# gld_schematic_v2.net
KiCad netlist of a schematic drawn in EasyEDA
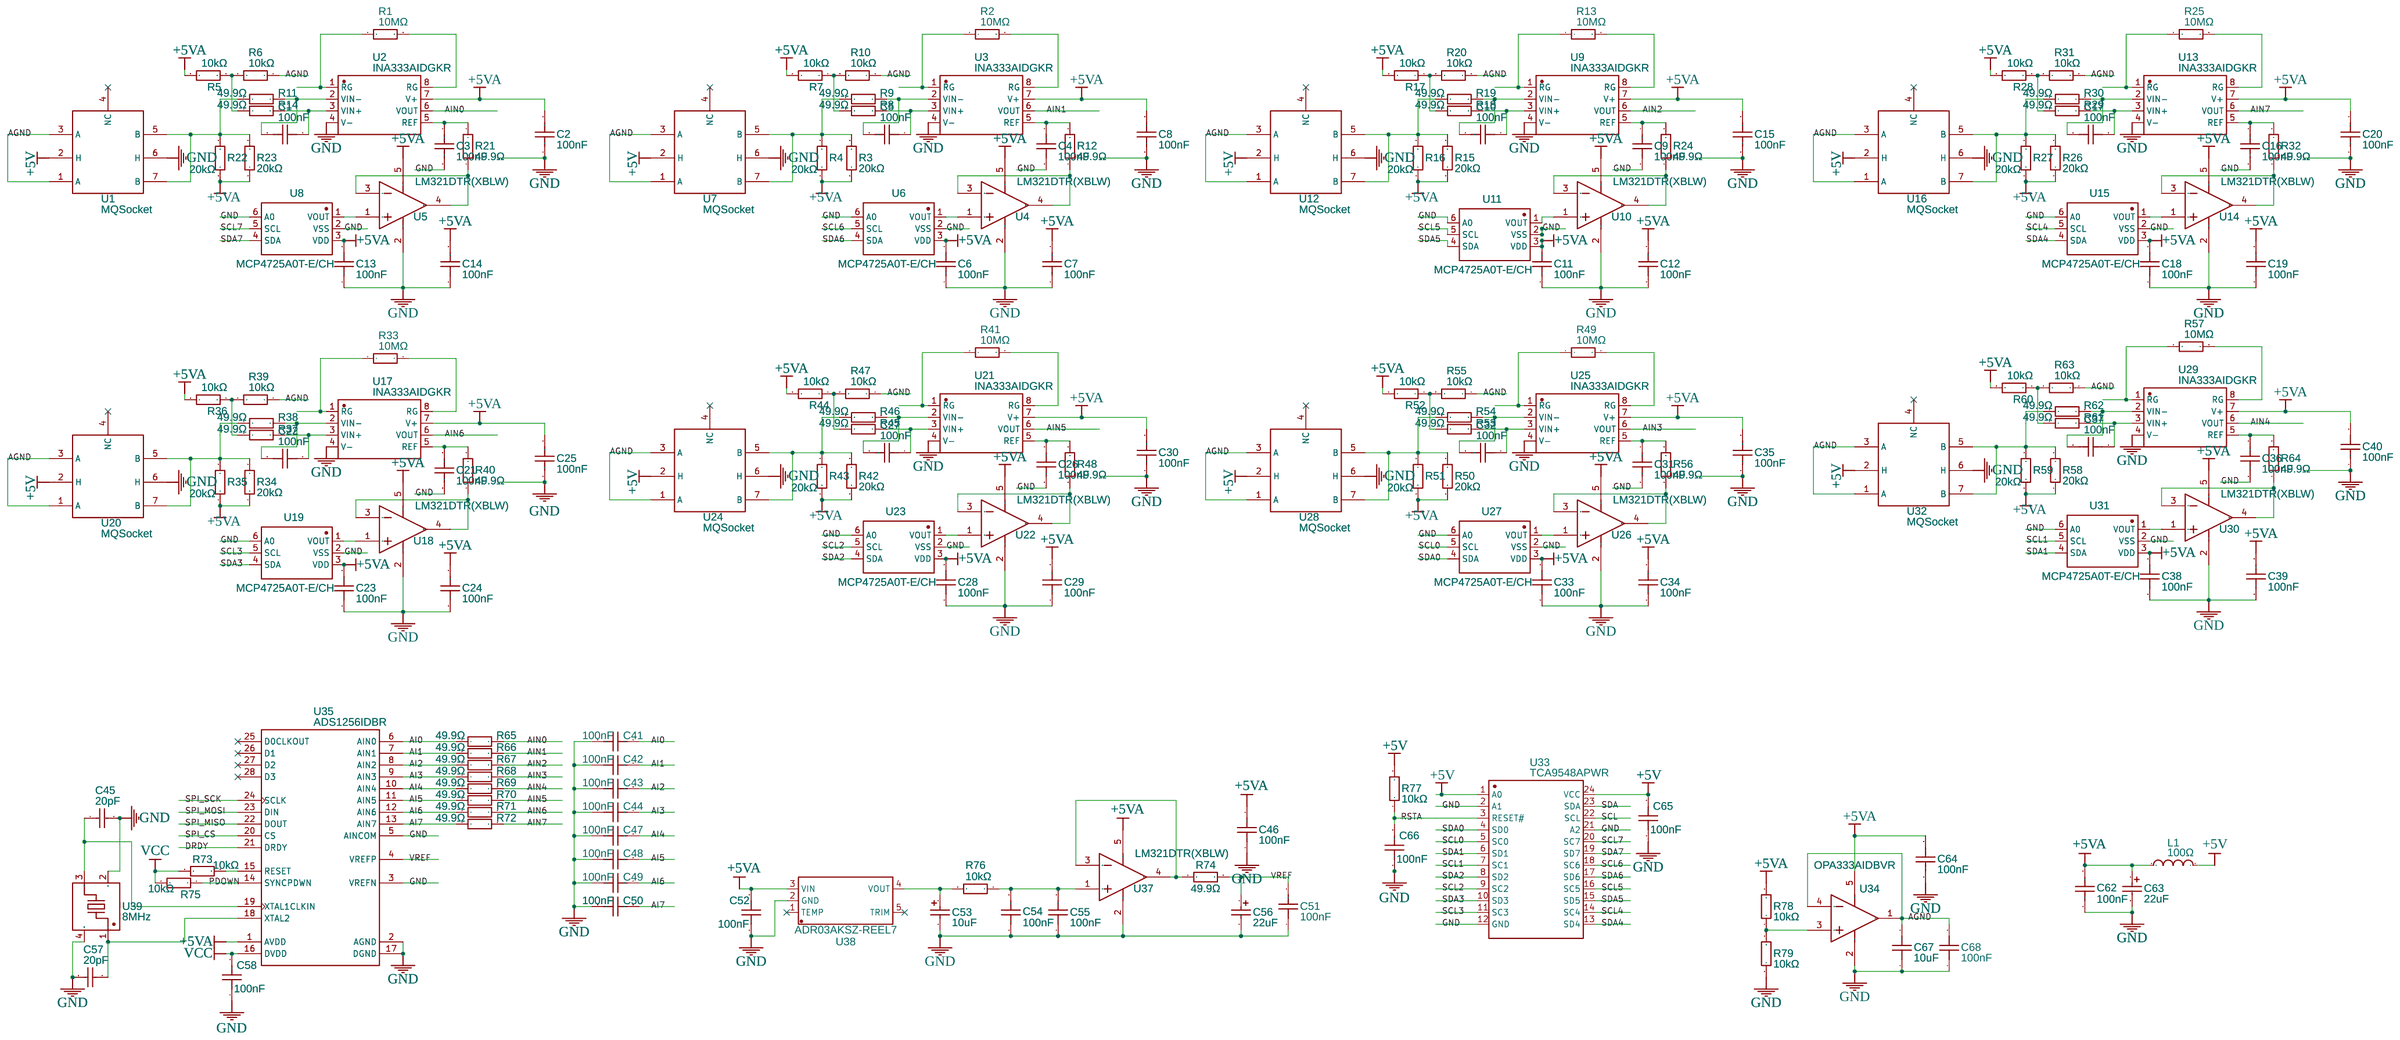
[diagram p0: Sheet_1]
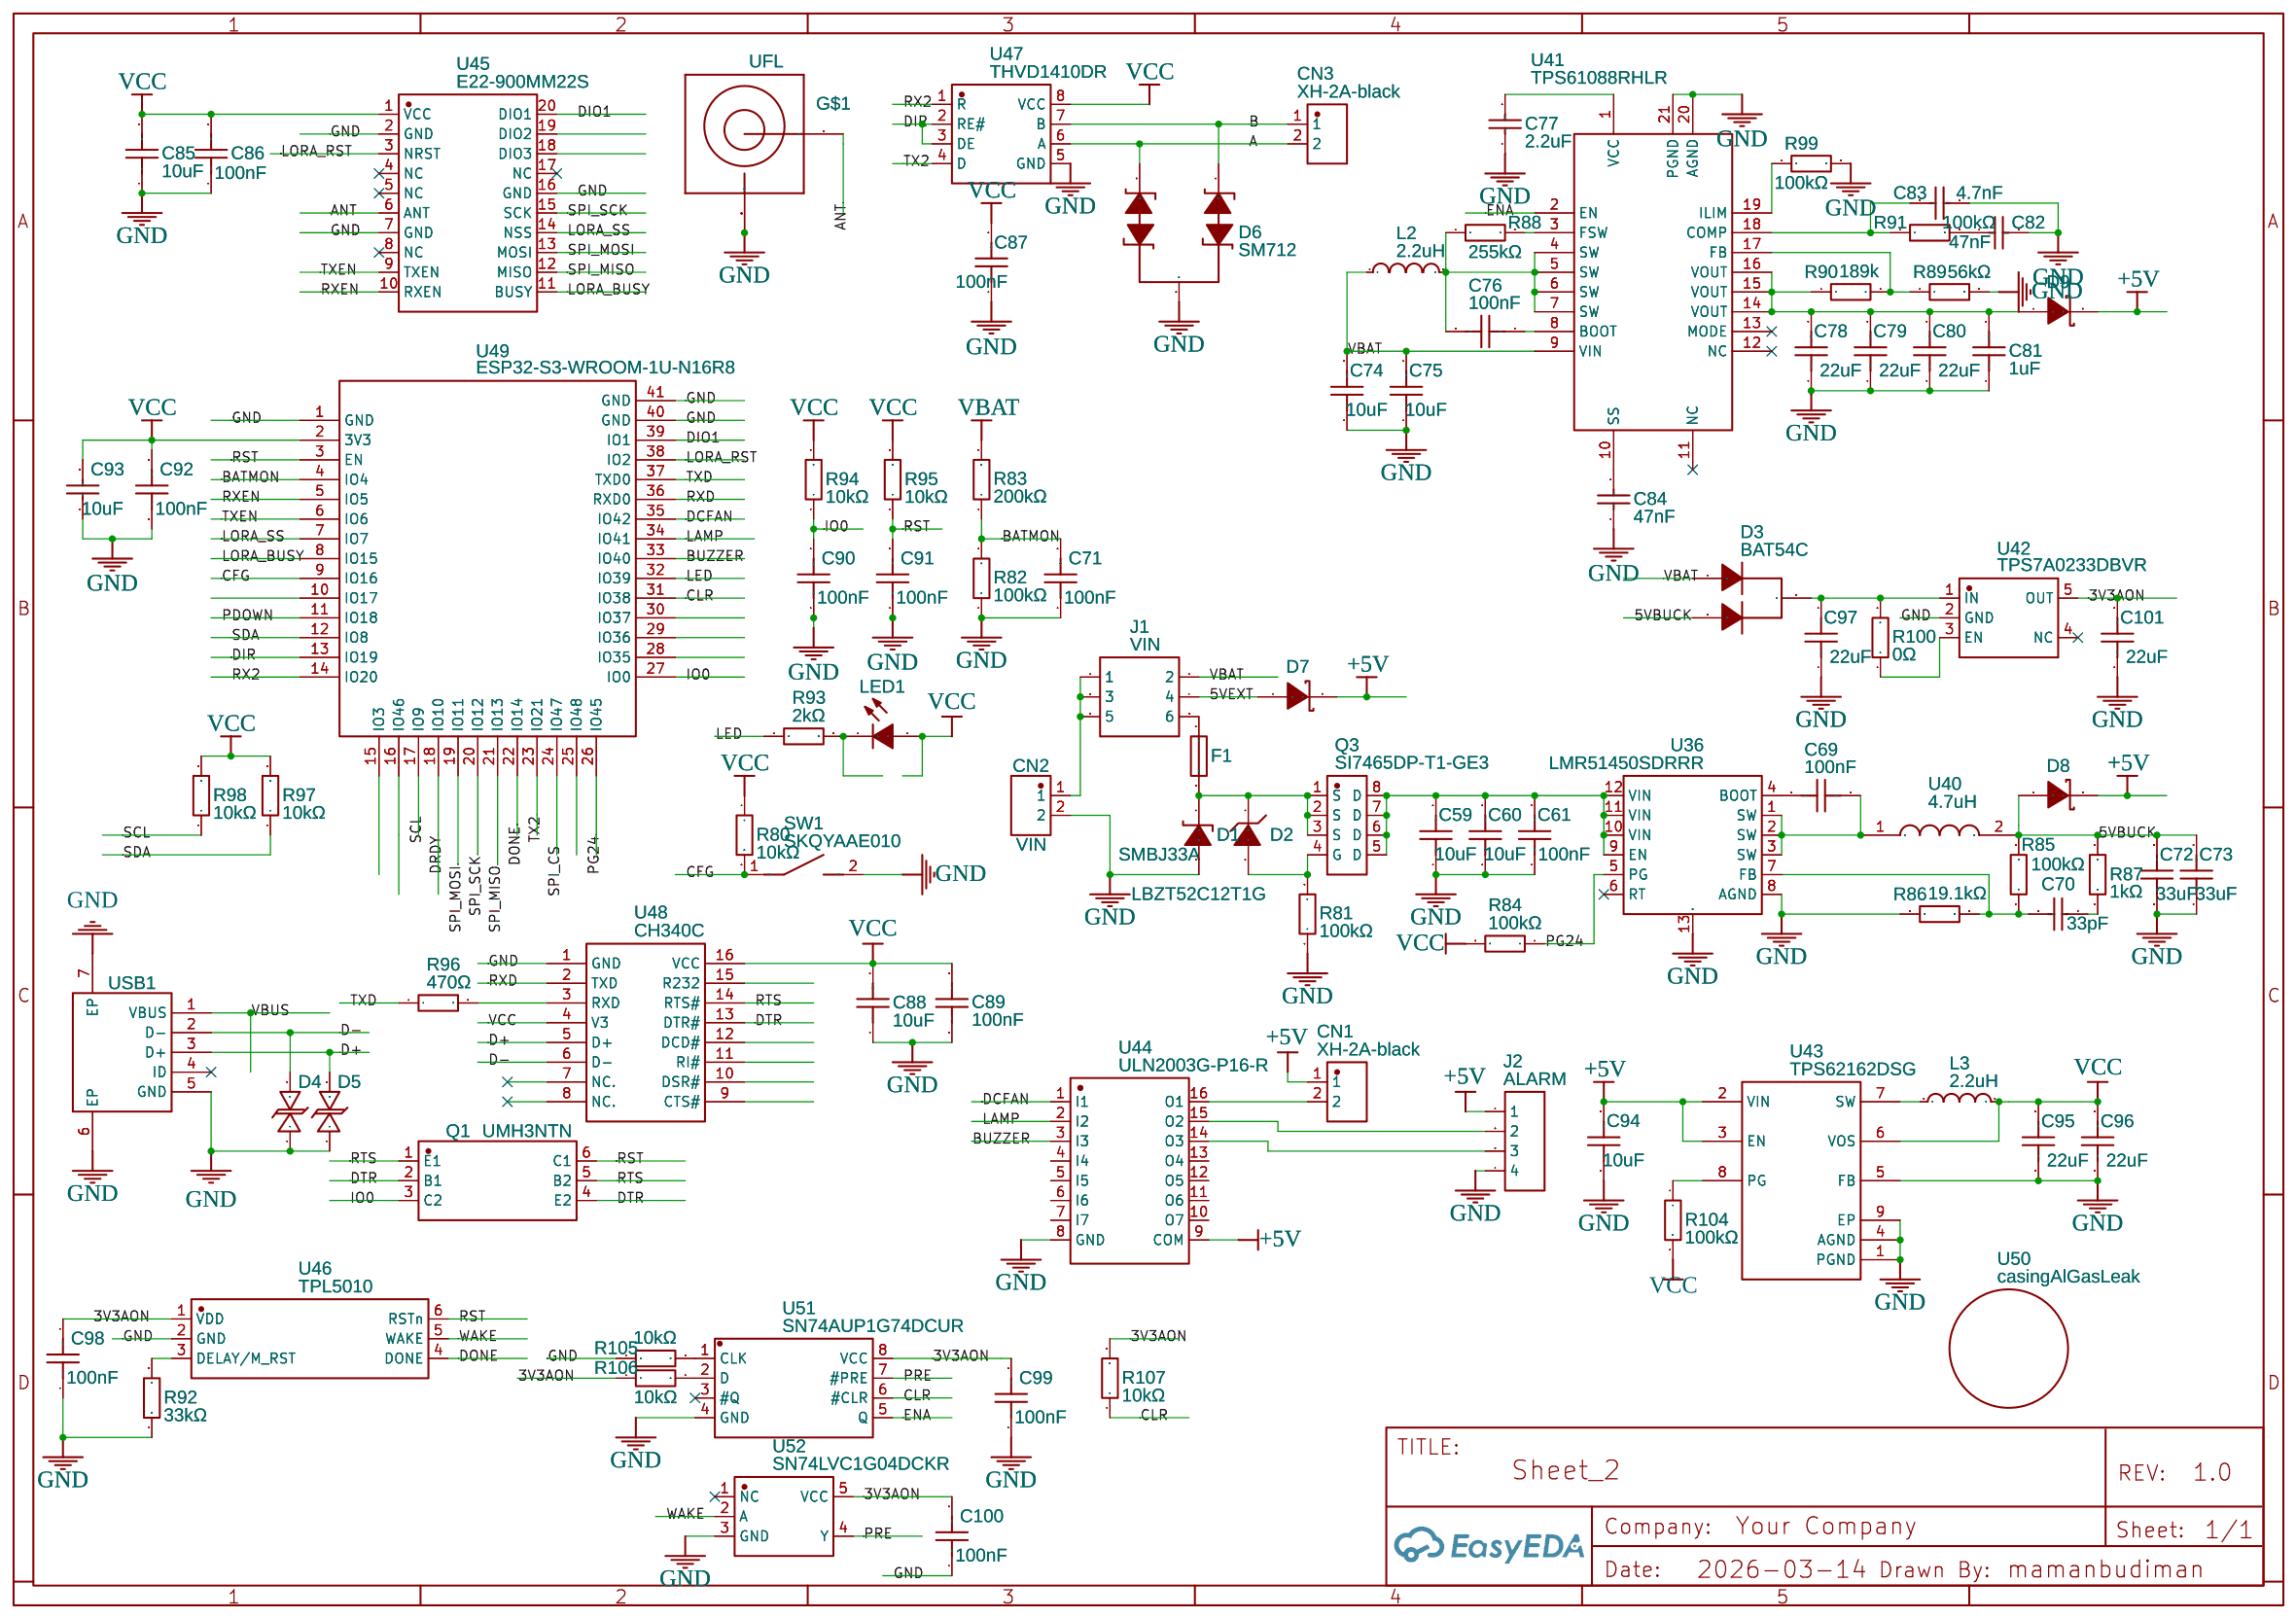
[diagram p1: Sheet_2]

(export (version "E")
  (design (tool "Eeschema 10.0.6"))
  (components
    (comp (ref "C1")
      (value "100nF")
      (fields
        (field (name "Manufacturer Part") "CL05B104KO5NNNC")
        (field (name "Manufacturer") "SAMSUNG(三星)")
      )
      (libsource (lib "") (part "CL05B104KO5NNNC"))
    )
    (comp (ref "C2")
      (value "100nF")
      (fields
        (field (name "Manufacturer Part") "CL05B104KO5NNNC")
        (field (name "Manufacturer") "SAMSUNG(三星)")
      )
      (libsource (lib "") (part "CL05B104KO5NNNC_1"))
    )
    (comp (ref "C3")
      (value "100nF")
      (fields
        (field (name "Manufacturer Part") "CL05B104KO5NNNC")
        (field (name "Manufacturer") "SAMSUNG(三星)")
      )
      (libsource (lib "") (part "CL05B104KO5NNNC_2"))
    )
    (comp (ref "C4")
      (value "100nF")
      (fields
        (field (name "Manufacturer Part") "CL05B104KO5NNNC")
        (field (name "Manufacturer") "SAMSUNG(三星)")
      )
      (libsource (lib "") (part "CL05B104KO5NNNC_2"))
    )
    (comp (ref "C5")
      (value "100nF")
      (fields
        (field (name "Manufacturer Part") "CL05B104KO5NNNC")
        (field (name "Manufacturer") "SAMSUNG(三星)")
      )
      (libsource (lib "") (part "CL05B104KO5NNNC"))
    )
    (comp (ref "C6")
      (value "100nF")
      (fields
        (field (name "Manufacturer Part") "CL05B104KO5NNNC")
        (field (name "Manufacturer") "SAMSUNG(三星)")
      )
      (libsource (lib "") (part "CL05B104KO5NNNC_1"))
    )
    (comp (ref "C7")
      (value "100nF")
      (fields
        (field (name "Manufacturer Part") "CL05B104KO5NNNC")
        (field (name "Manufacturer") "SAMSUNG(三星)")
      )
      (libsource (lib "") (part "CL05B104KO5NNNC_1"))
    )
    (comp (ref "C8")
      (value "100nF")
      (fields
        (field (name "Manufacturer Part") "CL05B104KO5NNNC")
        (field (name "Manufacturer") "SAMSUNG(三星)")
      )
      (libsource (lib "") (part "CL05B104KO5NNNC_1"))
    )
    (comp (ref "C9")
      (value "100nF")
      (fields
        (field (name "Manufacturer Part") "CL05B104KO5NNNC")
        (field (name "Manufacturer") "SAMSUNG(三星)")
      )
      (libsource (lib "") (part "CL05B104KO5NNNC_2"))
    )
    (comp (ref "C10")
      (value "100nF")
      (fields
        (field (name "Manufacturer Part") "CL05B104KO5NNNC")
        (field (name "Manufacturer") "SAMSUNG(三星)")
      )
      (libsource (lib "") (part "CL05B104KO5NNNC"))
    )
    (comp (ref "C11")
      (value "100nF")
      (fields
        (field (name "Manufacturer Part") "CL05B104KO5NNNC")
        (field (name "Manufacturer") "SAMSUNG(三星)")
      )
      (libsource (lib "") (part "CL05B104KO5NNNC_1"))
    )
    (comp (ref "C12")
      (value "100nF")
      (fields
        (field (name "Manufacturer Part") "CL05B104KO5NNNC")
        (field (name "Manufacturer") "SAMSUNG(三星)")
      )
      (libsource (lib "") (part "CL05B104KO5NNNC_1"))
    )
    (comp (ref "C13")
      (value "100nF")
      (fields
        (field (name "Manufacturer Part") "CL05B104KO5NNNC")
        (field (name "Manufacturer") "SAMSUNG(三星)")
      )
      (libsource (lib "") (part "CL05B104KO5NNNC_1"))
    )
    (comp (ref "C14")
      (value "100nF")
      (fields
        (field (name "Manufacturer Part") "CL05B104KO5NNNC")
        (field (name "Manufacturer") "SAMSUNG(三星)")
      )
      (libsource (lib "") (part "CL05B104KO5NNNC_1"))
    )
    (comp (ref "C15")
      (value "100nF")
      (fields
        (field (name "Manufacturer Part") "CL05B104KO5NNNC")
        (field (name "Manufacturer") "SAMSUNG(三星)")
      )
      (libsource (lib "") (part "CL05B104KO5NNNC_1"))
    )
    (comp (ref "C16")
      (value "100nF")
      (fields
        (field (name "Manufacturer Part") "CL05B104KO5NNNC")
        (field (name "Manufacturer") "SAMSUNG(三星)")
      )
      (libsource (lib "") (part "CL05B104KO5NNNC_2"))
    )
    (comp (ref "C17")
      (value "100nF")
      (fields
        (field (name "Manufacturer Part") "CL05B104KO5NNNC")
        (field (name "Manufacturer") "SAMSUNG(三星)")
      )
      (libsource (lib "") (part "CL05B104KO5NNNC"))
    )
    (comp (ref "C18")
      (value "100nF")
      (fields
        (field (name "Manufacturer Part") "CL05B104KO5NNNC")
        (field (name "Manufacturer") "SAMSUNG(三星)")
      )
      (libsource (lib "") (part "CL05B104KO5NNNC_1"))
    )
    (comp (ref "C19")
      (value "100nF")
      (fields
        (field (name "Manufacturer Part") "CL05B104KO5NNNC")
        (field (name "Manufacturer") "SAMSUNG(三星)")
      )
      (libsource (lib "") (part "CL05B104KO5NNNC_1"))
    )
    (comp (ref "C20")
      (value "100nF")
      (fields
        (field (name "Manufacturer Part") "CL05B104KO5NNNC")
        (field (name "Manufacturer") "SAMSUNG(三星)")
      )
      (libsource (lib "") (part "CL05B104KO5NNNC_1"))
    )
    (comp (ref "C21")
      (value "100nF")
      (fields
        (field (name "Manufacturer Part") "CL05B104KO5NNNC")
        (field (name "Manufacturer") "SAMSUNG(三星)")
      )
      (libsource (lib "") (part "CL05B104KO5NNNC_2"))
    )
    (comp (ref "C22")
      (value "100nF")
      (fields
        (field (name "Manufacturer Part") "CL05B104KO5NNNC")
        (field (name "Manufacturer") "SAMSUNG(三星)")
      )
      (libsource (lib "") (part "CL05B104KO5NNNC"))
    )
    (comp (ref "C23")
      (value "100nF")
      (fields
        (field (name "Manufacturer Part") "CL05B104KO5NNNC")
        (field (name "Manufacturer") "SAMSUNG(三星)")
      )
      (libsource (lib "") (part "CL05B104KO5NNNC_1"))
    )
    (comp (ref "C24")
      (value "100nF")
      (fields
        (field (name "Manufacturer Part") "CL05B104KO5NNNC")
        (field (name "Manufacturer") "SAMSUNG(三星)")
      )
      (libsource (lib "") (part "CL05B104KO5NNNC_1"))
    )
    (comp (ref "C25")
      (value "100nF")
      (fields
        (field (name "Manufacturer Part") "CL05B104KO5NNNC")
        (field (name "Manufacturer") "SAMSUNG(三星)")
      )
      (libsource (lib "") (part "CL05B104KO5NNNC_1"))
    )
    (comp (ref "C26")
      (value "100nF")
      (fields
        (field (name "Manufacturer Part") "CL05B104KO5NNNC")
        (field (name "Manufacturer") "SAMSUNG(三星)")
      )
      (libsource (lib "") (part "CL05B104KO5NNNC_2"))
    )
    (comp (ref "C27")
      (value "100nF")
      (fields
        (field (name "Manufacturer Part") "CL05B104KO5NNNC")
        (field (name "Manufacturer") "SAMSUNG(三星)")
      )
      (libsource (lib "") (part "CL05B104KO5NNNC"))
    )
    (comp (ref "C28")
      (value "100nF")
      (fields
        (field (name "Manufacturer Part") "CL05B104KO5NNNC")
        (field (name "Manufacturer") "SAMSUNG(三星)")
      )
      (libsource (lib "") (part "CL05B104KO5NNNC_1"))
    )
    (comp (ref "C29")
      (value "100nF")
      (fields
        (field (name "Manufacturer Part") "CL05B104KO5NNNC")
        (field (name "Manufacturer") "SAMSUNG(三星)")
      )
      (libsource (lib "") (part "CL05B104KO5NNNC_1"))
    )
    (comp (ref "C30")
      (value "100nF")
      (fields
        (field (name "Manufacturer Part") "CL05B104KO5NNNC")
        (field (name "Manufacturer") "SAMSUNG(三星)")
      )
      (libsource (lib "") (part "CL05B104KO5NNNC_1"))
    )
    (comp (ref "C31")
      (value "100nF")
      (fields
        (field (name "Manufacturer Part") "CL05B104KO5NNNC")
        (field (name "Manufacturer") "SAMSUNG(三星)")
      )
      (libsource (lib "") (part "CL05B104KO5NNNC_2"))
    )
    (comp (ref "C32")
      (value "100nF")
      (fields
        (field (name "Manufacturer Part") "CL05B104KO5NNNC")
        (field (name "Manufacturer") "SAMSUNG(三星)")
      )
      (libsource (lib "") (part "CL05B104KO5NNNC"))
    )
    (comp (ref "C33")
      (value "100nF")
      (fields
        (field (name "Manufacturer Part") "CL05B104KO5NNNC")
        (field (name "Manufacturer") "SAMSUNG(三星)")
      )
      (libsource (lib "") (part "CL05B104KO5NNNC_1"))
    )
    (comp (ref "C34")
      (value "100nF")
      (fields
        (field (name "Manufacturer Part") "CL05B104KO5NNNC")
        (field (name "Manufacturer") "SAMSUNG(三星)")
      )
      (libsource (lib "") (part "CL05B104KO5NNNC_1"))
    )
    (comp (ref "C35")
      (value "100nF")
      (fields
        (field (name "Manufacturer Part") "CL05B104KO5NNNC")
        (field (name "Manufacturer") "SAMSUNG(三星)")
      )
      (libsource (lib "") (part "CL05B104KO5NNNC_1"))
    )
    (comp (ref "C36")
      (value "100nF")
      (fields
        (field (name "Manufacturer Part") "CL05B104KO5NNNC")
        (field (name "Manufacturer") "SAMSUNG(三星)")
      )
      (libsource (lib "") (part "CL05B104KO5NNNC_2"))
    )
    (comp (ref "C37")
      (value "100nF")
      (fields
        (field (name "Manufacturer Part") "CL05B104KO5NNNC")
        (field (name "Manufacturer") "SAMSUNG(三星)")
      )
      (libsource (lib "") (part "CL05B104KO5NNNC"))
    )
    (comp (ref "C38")
      (value "100nF")
      (fields
        (field (name "Manufacturer Part") "CL05B104KO5NNNC")
        (field (name "Manufacturer") "SAMSUNG(三星)")
      )
      (libsource (lib "") (part "CL05B104KO5NNNC_1"))
    )
    (comp (ref "C39")
      (value "100nF")
      (fields
        (field (name "Manufacturer Part") "CL05B104KO5NNNC")
        (field (name "Manufacturer") "SAMSUNG(三星)")
      )
      (libsource (lib "") (part "CL05B104KO5NNNC_1"))
    )
    (comp (ref "C40")
      (value "100nF")
      (fields
        (field (name "Manufacturer Part") "CL05B104KO5NNNC")
        (field (name "Manufacturer") "SAMSUNG(三星)")
      )
      (libsource (lib "") (part "CL05B104KO5NNNC_1"))
    )
    (comp (ref "C41")
      (value "100nF")
      (fields
        (field (name "Manufacturer Part") "CL05B104KO5NNNC")
        (field (name "Manufacturer") "SAMSUNG(三星)")
      )
      (libsource (lib "") (part "CL05B104KO5NNNC_3"))
    )
    (comp (ref "C42")
      (value "100nF")
      (fields
        (field (name "Manufacturer Part") "CL05B104KO5NNNC")
        (field (name "Manufacturer") "SAMSUNG(三星)")
      )
      (libsource (lib "") (part "CL05B104KO5NNNC_3"))
    )
    (comp (ref "C43")
      (value "100nF")
      (fields
        (field (name "Manufacturer Part") "CL05B104KO5NNNC")
        (field (name "Manufacturer") "SAMSUNG(三星)")
      )
      (libsource (lib "") (part "CL05B104KO5NNNC_3"))
    )
    (comp (ref "C44")
      (value "100nF")
      (fields
        (field (name "Manufacturer Part") "CL05B104KO5NNNC")
        (field (name "Manufacturer") "SAMSUNG(三星)")
      )
      (libsource (lib "") (part "CL05B104KO5NNNC_3"))
    )
    (comp (ref "C45")
      (value "20pF")
      (fields (field (name "Manufacturer Part") "0402CG200J500NT") (field (name "Manufacturer") "FH(风华)"))
      (libsource (lib "") (part "0402CG200J500NT"))
    )
    (comp (ref "C46")
      (value "100nF")
      (fields
        (field (name "Manufacturer Part") "CL05B104KO5NNNC")
        (field (name "Manufacturer") "SAMSUNG(三星)")
      )
      (libsource (lib "") (part "CL05B104KO5NNNC_1"))
    )
    (comp (ref "C47")
      (value "100nF")
      (fields
        (field (name "Manufacturer Part") "CL05B104KO5NNNC")
        (field (name "Manufacturer") "SAMSUNG(三星)")
      )
      (libsource (lib "") (part "CL05B104KO5NNNC_3"))
    )
    (comp (ref "C48")
      (value "100nF")
      (fields
        (field (name "Manufacturer Part") "CL05B104KO5NNNC")
        (field (name "Manufacturer") "SAMSUNG(三星)")
      )
      (libsource (lib "") (part "CL05B104KO5NNNC_3"))
    )
    (comp (ref "C49")
      (value "100nF")
      (fields
        (field (name "Manufacturer Part") "CL05B104KO5NNNC")
        (field (name "Manufacturer") "SAMSUNG(三星)")
      )
      (libsource (lib "") (part "CL05B104KO5NNNC_3"))
    )
    (comp (ref "C50")
      (value "100nF")
      (fields
        (field (name "Manufacturer Part") "CL05B104KO5NNNC")
        (field (name "Manufacturer") "SAMSUNG(三星)")
      )
      (libsource (lib "") (part "CL05B104KO5NNNC_3"))
    )
    (comp (ref "C51")
      (value "100nF")
      (fields
        (field (name "Manufacturer Part") "CL05B104KO5NNNC")
        (field (name "Manufacturer") "SAMSUNG(三星)")
      )
      (libsource (lib "") (part "CL05B104KO5NNNC_1"))
    )
    (comp (ref "C52")
      (value "100nF")
      (fields
        (field (name "Manufacturer Part") "CL05B104KO5NNNC")
        (field (name "Manufacturer") "SAMSUNG(三星)")
      )
      (libsource (lib "") (part "CL05B104KO5NNNC_1"))
    )
    (comp (ref "C53")
      (value "10uF")
      (fields (field (name "Manufacturer Part") "TAJA106K016RNJ") (field (name "Manufacturer") "Kyocera AVX"))
      (libsource (lib "") (part "TAJA106K016RNJ"))
    )
    (comp (ref "C54")
      (value "100nF")
      (fields
        (field (name "Manufacturer Part") "CL05B104KO5NNNC")
        (field (name "Manufacturer") "SAMSUNG(三星)")
      )
      (libsource (lib "") (part "CL05B104KO5NNNC_1"))
    )
    (comp (ref "C55")
      (value "100nF")
      (fields
        (field (name "Manufacturer Part") "CL05B104KO5NNNC")
        (field (name "Manufacturer") "SAMSUNG(三星)")
      )
      (libsource (lib "") (part "CL05B104KO5NNNC_1"))
    )
    (comp (ref "C56")
      (value "22uF")
      (fields (field (name "Manufacturer Part") "TAJA226M010RNJ") (field (name "Manufacturer") "Kyocera AVX"))
      (libsource (lib "") (part "TAJA226M010RNJ"))
    )
    (comp (ref "C57")
      (value "20pF")
      (fields (field (name "Manufacturer Part") "0402CG200J500NT") (field (name "Manufacturer") "FH(风华)"))
      (libsource (lib "") (part "0402CG200J500NT"))
    )
    (comp (ref "C58")
      (value "100nF")
      (fields (field (name "Manufacturer Part") "CC0603KRX7R9BB104") (field (name "Manufacturer") "YAGEO"))
      (libsource (lib "") (part "CC0603KRX7R9BB104"))
    )
    (comp (ref "C62")
      (value "100nF")
      (fields
        (field (name "Manufacturer Part") "CL05B104KO5NNNC")
        (field (name "Manufacturer") "SAMSUNG(三星)")
      )
      (libsource (lib "") (part "CL05B104KO5NNNC_1"))
    )
    (comp (ref "C63")
      (value "22uF")
      (fields (field (name "Manufacturer Part") "TAJA226M010RNJ") (field (name "Manufacturer") "Kyocera AVX"))
      (libsource (lib "") (part "TAJA226M010RNJ"))
    )
    (comp (ref "C64")
      (value "100nF")
      (fields
        (field (name "Manufacturer Part") "CC0603KRX7R9BB104")
        (field (name "Manufacturer") "YAGEO(国巨)")
      )
      (libsource (lib "") (part "CC0603KRX7R9BB104"))
    )
    (comp (ref "C65")
      (value "100nF")
      (fields (field (name "Manufacturer Part") "CC0603KRX7R9BB104") (field (name "Manufacturer") "YAGEO"))
      (libsource (lib "") (part "CC0603KRX7R9BB104"))
    )
    (comp (ref "C66")
      (value "100nF")
      (fields (field (name "Manufacturer Part") "CC0603KRX7R9BB104") (field (name "Manufacturer") "YAGEO"))
      (libsource (lib "") (part "CC0603KRX7R9BB104"))
    )
    (comp (ref "C67")
      (value "10uF")
      (fields
        (field (name "Manufacturer Part") "CL10A106KP8NNNC")
        (field (name "Manufacturer") "SAMSUNG(三星)")
      )
      (libsource (lib "") (part "CL10A106KP8NNNC"))
    )
    (comp (ref "C68")
      (value "100nF")
      (fields
        (field (name "Manufacturer Part") "CC0603KRX7R9BB104")
        (field (name "Manufacturer") "YAGEO(国巨)")
      )
      (libsource (lib "") (part "CC0603KRX7R9BB104"))
    )
    (comp (ref "L1")
      (value "100Ω")
      (fields (field (name "Manufacturer Part") "GZ2012D101TF") (field (name "Manufacturer") "Sunlord(顺络)"))
      (libsource (lib "") (part "GZ2012D101TF"))
    )
    (comp (ref "R1")
      (value "10MΩ")
      (fields
        (field (name "Manufacturer Part") "0603WAF1005T5E")
        (field (name "Manufacturer") "UNI-ROYAL(厚声)")
      )
      (libsource (lib "") (part "0603WAF1005T5E"))
    )
    (comp (ref "R2")
      (value "10MΩ")
      (fields
        (field (name "Manufacturer Part") "0603WAF1005T5E")
        (field (name "Manufacturer") "UNI-ROYAL(厚声)")
      )
      (libsource (lib "") (part "0603WAF1005T5E"))
    )
    (comp (ref "R3")
      (value "20kΩ")
      (fields
        (field (name "Manufacturer Part") "0603WAF2002T5E")
        (field (name "Manufacturer") "UNI-ROYAL(厚声)")
      )
      (libsource (lib "") (part "0603WAF2002T5E"))
    )
    (comp (ref "R4")
      (value "20kΩ")
      (fields
        (field (name "Manufacturer Part") "0603WAF2002T5E")
        (field (name "Manufacturer") "UNI-ROYAL(厚声)")
      )
      (libsource (lib "") (part "0603WAF2002T5E"))
    )
    (comp (ref "R5")
      (value "10kΩ")
      (fields (field (name "Manufacturer Part") "RT0603BRD0710KL") (field (name "Manufacturer") "YAGEO(国巨)"))
      (libsource (lib "") (part "RT0603BRD0710KL"))
    )
    (comp (ref "R6")
      (value "10kΩ")
      (fields (field (name "Manufacturer Part") "RT0603BRD0710KL") (field (name "Manufacturer") "YAGEO(国巨)"))
      (libsource (lib "") (part "RT0603BRD0710KL"))
    )
    (comp (ref "R7")
      (value "10kΩ")
      (fields (field (name "Manufacturer Part") "RT0603BRD0710KL") (field (name "Manufacturer") "YAGEO(国巨)"))
      (libsource (lib "") (part "RT0603BRD0710KL"))
    )
    (comp (ref "R8")
      (value "49.9Ω")
      (fields (field (name "Manufacturer Part") "RC-02K49R9FT") (field (name "Manufacturer") "FH(风华)"))
      (libsource (lib "") (part "RC-02K49R9FT"))
    )
    (comp (ref "R9")
      (value "49.9Ω")
      (fields (field (name "Manufacturer Part") "RC-02K49R9FT") (field (name "Manufacturer") "FH(风华)"))
      (libsource (lib "") (part "RC-02K49R9FT"))
    )
    (comp (ref "R10")
      (value "10kΩ")
      (fields (field (name "Manufacturer Part") "RT0603BRD0710KL") (field (name "Manufacturer") "YAGEO(国巨)"))
      (libsource (lib "") (part "RT0603BRD0710KL"))
    )
    (comp (ref "R11")
      (value "49.9Ω")
      (fields (field (name "Manufacturer Part") "RC-02K49R9FT") (field (name "Manufacturer") "FH(风华)"))
      (libsource (lib "") (part "RC-02K49R9FT"))
    )
    (comp (ref "R12")
      (value "49.9Ω")
      (fields (field (name "Manufacturer Part") "RC-02K49R9FT") (field (name "Manufacturer") "FH(风华)"))
      (libsource (lib "") (part "RC-02K49R9FT_1"))
    )
    (comp (ref "R13")
      (value "10MΩ")
      (fields
        (field (name "Manufacturer Part") "0603WAF1005T5E")
        (field (name "Manufacturer") "UNI-ROYAL(厚声)")
      )
      (libsource (lib "") (part "0603WAF1005T5E"))
    )
    (comp (ref "R14")
      (value "49.9Ω")
      (fields (field (name "Manufacturer Part") "RC-02K49R9FT") (field (name "Manufacturer") "FH(风华)"))
      (libsource (lib "") (part "RC-02K49R9FT"))
    )
    (comp (ref "R15")
      (value "20kΩ")
      (fields
        (field (name "Manufacturer Part") "0603WAF2002T5E")
        (field (name "Manufacturer") "UNI-ROYAL(厚声)")
      )
      (libsource (lib "") (part "0603WAF2002T5E"))
    )
    (comp (ref "R16")
      (value "20kΩ")
      (fields
        (field (name "Manufacturer Part") "0603WAF2002T5E")
        (field (name "Manufacturer") "UNI-ROYAL(厚声)")
      )
      (libsource (lib "") (part "0603WAF2002T5E"))
    )
    (comp (ref "R17")
      (value "10kΩ")
      (fields (field (name "Manufacturer Part") "RT0603BRD0710KL") (field (name "Manufacturer") "YAGEO(国巨)"))
      (libsource (lib "") (part "RT0603BRD0710KL"))
    )
    (comp (ref "R18")
      (value "49.9Ω")
      (fields (field (name "Manufacturer Part") "RC-02K49R9FT") (field (name "Manufacturer") "FH(风华)"))
      (libsource (lib "") (part "RC-02K49R9FT"))
    )
    (comp (ref "R19")
      (value "49.9Ω")
      (fields (field (name "Manufacturer Part") "RC-02K49R9FT") (field (name "Manufacturer") "FH(风华)"))
      (libsource (lib "") (part "RC-02K49R9FT"))
    )
    (comp (ref "R20")
      (value "10kΩ")
      (fields (field (name "Manufacturer Part") "RT0603BRD0710KL") (field (name "Manufacturer") "YAGEO(国巨)"))
      (libsource (lib "") (part "RT0603BRD0710KL"))
    )
    (comp (ref "R21")
      (value "49.9Ω")
      (fields (field (name "Manufacturer Part") "RC-02K49R9FT") (field (name "Manufacturer") "FH(风华)"))
      (libsource (lib "") (part "RC-02K49R9FT_1"))
    )
    (comp (ref "R22")
      (value "20kΩ")
      (fields
        (field (name "Manufacturer Part") "0603WAF2002T5E")
        (field (name "Manufacturer") "UNI-ROYAL(厚声)")
      )
      (libsource (lib "") (part "0603WAF2002T5E"))
    )
    (comp (ref "R23")
      (value "20kΩ")
      (fields
        (field (name "Manufacturer Part") "0603WAF2002T5E")
        (field (name "Manufacturer") "UNI-ROYAL(厚声)")
      )
      (libsource (lib "") (part "0603WAF2002T5E"))
    )
    (comp (ref "R24")
      (value "49.9Ω")
      (fields (field (name "Manufacturer Part") "RC-02K49R9FT") (field (name "Manufacturer") "FH(风华)"))
      (libsource (lib "") (part "RC-02K49R9FT_1"))
    )
    (comp (ref "R25")
      (value "10MΩ")
      (fields
        (field (name "Manufacturer Part") "0603WAF1005T5E")
        (field (name "Manufacturer") "UNI-ROYAL(厚声)")
      )
      (libsource (lib "") (part "0603WAF1005T5E"))
    )
    (comp (ref "R26")
      (value "20kΩ")
      (fields
        (field (name "Manufacturer Part") "0603WAF2002T5E")
        (field (name "Manufacturer") "UNI-ROYAL(厚声)")
      )
      (libsource (lib "") (part "0603WAF2002T5E"))
    )
    (comp (ref "R27")
      (value "20kΩ")
      (fields
        (field (name "Manufacturer Part") "0603WAF2002T5E")
        (field (name "Manufacturer") "UNI-ROYAL(厚声)")
      )
      (libsource (lib "") (part "0603WAF2002T5E"))
    )
    (comp (ref "R28")
      (value "10kΩ")
      (fields (field (name "Manufacturer Part") "RT0603BRD0710KL") (field (name "Manufacturer") "YAGEO(国巨)"))
      (libsource (lib "") (part "RT0603BRD0710KL"))
    )
    (comp (ref "R29")
      (value "49.9Ω")
      (fields (field (name "Manufacturer Part") "RC-02K49R9FT") (field (name "Manufacturer") "FH(风华)"))
      (libsource (lib "") (part "RC-02K49R9FT"))
    )
    (comp (ref "R30")
      (value "49.9Ω")
      (fields (field (name "Manufacturer Part") "RC-02K49R9FT") (field (name "Manufacturer") "FH(风华)"))
      (libsource (lib "") (part "RC-02K49R9FT"))
    )
    (comp (ref "R31")
      (value "10kΩ")
      (fields (field (name "Manufacturer Part") "RT0603BRD0710KL") (field (name "Manufacturer") "YAGEO(国巨)"))
      (libsource (lib "") (part "RT0603BRD0710KL"))
    )
    (comp (ref "R32")
      (value "49.9Ω")
      (fields (field (name "Manufacturer Part") "RC-02K49R9FT") (field (name "Manufacturer") "FH(风华)"))
      (libsource (lib "") (part "RC-02K49R9FT_1"))
    )
    (comp (ref "R33")
      (value "10MΩ")
      (fields
        (field (name "Manufacturer Part") "0603WAF1005T5E")
        (field (name "Manufacturer") "UNI-ROYAL(厚声)")
      )
      (libsource (lib "") (part "0603WAF1005T5E"))
    )
    (comp (ref "R34")
      (value "20kΩ")
      (fields
        (field (name "Manufacturer Part") "0603WAF2002T5E")
        (field (name "Manufacturer") "UNI-ROYAL(厚声)")
      )
      (libsource (lib "") (part "0603WAF2002T5E"))
    )
    (comp (ref "R35")
      (value "20kΩ")
      (fields
        (field (name "Manufacturer Part") "0603WAF2002T5E")
        (field (name "Manufacturer") "UNI-ROYAL(厚声)")
      )
      (libsource (lib "") (part "0603WAF2002T5E"))
    )
    (comp (ref "R36")
      (value "10kΩ")
      (fields (field (name "Manufacturer Part") "RT0603BRD0710KL") (field (name "Manufacturer") "YAGEO(国巨)"))
      (libsource (lib "") (part "RT0603BRD0710KL"))
    )
    (comp (ref "R37")
      (value "49.9Ω")
      (fields (field (name "Manufacturer Part") "RC-02K49R9FT") (field (name "Manufacturer") "FH(风华)"))
      (libsource (lib "") (part "RC-02K49R9FT"))
    )
    (comp (ref "R38")
      (value "49.9Ω")
      (fields (field (name "Manufacturer Part") "RC-02K49R9FT") (field (name "Manufacturer") "FH(风华)"))
      (libsource (lib "") (part "RC-02K49R9FT"))
    )
    (comp (ref "R39")
      (value "10kΩ")
      (fields (field (name "Manufacturer Part") "RT0603BRD0710KL") (field (name "Manufacturer") "YAGEO(国巨)"))
      (libsource (lib "") (part "RT0603BRD0710KL"))
    )
    (comp (ref "R40")
      (value "49.9Ω")
      (fields (field (name "Manufacturer Part") "RC-02K49R9FT") (field (name "Manufacturer") "FH(风华)"))
      (libsource (lib "") (part "RC-02K49R9FT_1"))
    )
    (comp (ref "R41")
      (value "10MΩ")
      (fields
        (field (name "Manufacturer Part") "0603WAF1005T5E")
        (field (name "Manufacturer") "UNI-ROYAL(厚声)")
      )
      (libsource (lib "") (part "0603WAF1005T5E"))
    )
    (comp (ref "R42")
      (value "20kΩ")
      (fields
        (field (name "Manufacturer Part") "0603WAF2002T5E")
        (field (name "Manufacturer") "UNI-ROYAL(厚声)")
      )
      (libsource (lib "") (part "0603WAF2002T5E"))
    )
    (comp (ref "R43")
      (value "20kΩ")
      (fields
        (field (name "Manufacturer Part") "0603WAF2002T5E")
        (field (name "Manufacturer") "UNI-ROYAL(厚声)")
      )
      (libsource (lib "") (part "0603WAF2002T5E"))
    )
    (comp (ref "R44")
      (value "10kΩ")
      (fields (field (name "Manufacturer Part") "RT0603BRD0710KL") (field (name "Manufacturer") "YAGEO(国巨)"))
      (libsource (lib "") (part "RT0603BRD0710KL"))
    )
    (comp (ref "R45")
      (value "49.9Ω")
      (fields (field (name "Manufacturer Part") "RC-02K49R9FT") (field (name "Manufacturer") "FH(风华)"))
      (libsource (lib "") (part "RC-02K49R9FT"))
    )
    (comp (ref "R46")
      (value "49.9Ω")
      (fields (field (name "Manufacturer Part") "RC-02K49R9FT") (field (name "Manufacturer") "FH(风华)"))
      (libsource (lib "") (part "RC-02K49R9FT"))
    )
    (comp (ref "R47")
      (value "10kΩ")
      (fields (field (name "Manufacturer Part") "RT0603BRD0710KL") (field (name "Manufacturer") "YAGEO(国巨)"))
      (libsource (lib "") (part "RT0603BRD0710KL"))
    )
    (comp (ref "R48")
      (value "49.9Ω")
      (fields (field (name "Manufacturer Part") "RC-02K49R9FT") (field (name "Manufacturer") "FH(风华)"))
      (libsource (lib "") (part "RC-02K49R9FT_1"))
    )
    (comp (ref "R49")
      (value "10MΩ")
      (fields
        (field (name "Manufacturer Part") "0603WAF1005T5E")
        (field (name "Manufacturer") "UNI-ROYAL(厚声)")
      )
      (libsource (lib "") (part "0603WAF1005T5E"))
    )
    (comp (ref "R50")
      (value "20kΩ")
      (fields
        (field (name "Manufacturer Part") "0603WAF2002T5E")
        (field (name "Manufacturer") "UNI-ROYAL(厚声)")
      )
      (libsource (lib "") (part "0603WAF2002T5E"))
    )
    (comp (ref "R51")
      (value "20kΩ")
      (fields
        (field (name "Manufacturer Part") "0603WAF2002T5E")
        (field (name "Manufacturer") "UNI-ROYAL(厚声)")
      )
      (libsource (lib "") (part "0603WAF2002T5E"))
    )
    (comp (ref "R52")
      (value "10kΩ")
      (fields (field (name "Manufacturer Part") "RT0603BRD0710KL") (field (name "Manufacturer") "YAGEO(国巨)"))
      (libsource (lib "") (part "RT0603BRD0710KL"))
    )
    (comp (ref "R53")
      (value "49.9Ω")
      (fields (field (name "Manufacturer Part") "RC-02K49R9FT") (field (name "Manufacturer") "FH(风华)"))
      (libsource (lib "") (part "RC-02K49R9FT"))
    )
    (comp (ref "R54")
      (value "49.9Ω")
      (fields (field (name "Manufacturer Part") "RC-02K49R9FT") (field (name "Manufacturer") "FH(风华)"))
      (libsource (lib "") (part "RC-02K49R9FT"))
    )
    (comp (ref "R55")
      (value "10kΩ")
      (fields (field (name "Manufacturer Part") "RT0603BRD0710KL") (field (name "Manufacturer") "YAGEO(国巨)"))
      (libsource (lib "") (part "RT0603BRD0710KL"))
    )
    (comp (ref "R56")
      (value "49.9Ω")
      (fields (field (name "Manufacturer Part") "RC-02K49R9FT") (field (name "Manufacturer") "FH(风华)"))
      (libsource (lib "") (part "RC-02K49R9FT_1"))
    )
    (comp (ref "R57")
      (value "10MΩ")
      (fields
        (field (name "Manufacturer Part") "0603WAF1005T5E")
        (field (name "Manufacturer") "UNI-ROYAL(厚声)")
      )
      (libsource (lib "") (part "0603WAF1005T5E"))
    )
    (comp (ref "R58")
      (value "20kΩ")
      (fields
        (field (name "Manufacturer Part") "0603WAF2002T5E")
        (field (name "Manufacturer") "UNI-ROYAL(厚声)")
      )
      (libsource (lib "") (part "0603WAF2002T5E"))
    )
    (comp (ref "R59")
      (value "20kΩ")
      (fields
        (field (name "Manufacturer Part") "0603WAF2002T5E")
        (field (name "Manufacturer") "UNI-ROYAL(厚声)")
      )
      (libsource (lib "") (part "0603WAF2002T5E"))
    )
    (comp (ref "R60")
      (value "10kΩ")
      (fields (field (name "Manufacturer Part") "RT0603BRD0710KL") (field (name "Manufacturer") "YAGEO(国巨)"))
      (libsource (lib "") (part "RT0603BRD0710KL"))
    )
    (comp (ref "R61")
      (value "49.9Ω")
      (fields (field (name "Manufacturer Part") "RC-02K49R9FT") (field (name "Manufacturer") "FH(风华)"))
      (libsource (lib "") (part "RC-02K49R9FT"))
    )
    (comp (ref "R62")
      (value "49.9Ω")
      (fields (field (name "Manufacturer Part") "RC-02K49R9FT") (field (name "Manufacturer") "FH(风华)"))
      (libsource (lib "") (part "RC-02K49R9FT"))
    )
    (comp (ref "R63")
      (value "10kΩ")
      (fields (field (name "Manufacturer Part") "RT0603BRD0710KL") (field (name "Manufacturer") "YAGEO(国巨)"))
      (libsource (lib "") (part "RT0603BRD0710KL"))
    )
    (comp (ref "R64")
      (value "49.9Ω")
      (fields (field (name "Manufacturer Part") "RC-02K49R9FT") (field (name "Manufacturer") "FH(风华)"))
      (libsource (lib "") (part "RC-02K49R9FT_1"))
    )
    (comp (ref "R65")
      (value "49.9Ω")
      (fields (field (name "Manufacturer Part") "RC-02K49R9FT") (field (name "Manufacturer") "FH(风华)"))
      (libsource (lib "") (part "RC-02K49R9FT"))
    )
    (comp (ref "R66")
      (value "49.9Ω")
      (fields (field (name "Manufacturer Part") "RC-02K49R9FT") (field (name "Manufacturer") "FH(风华)"))
      (libsource (lib "") (part "RC-02K49R9FT"))
    )
    (comp (ref "R67")
      (value "49.9Ω")
      (fields (field (name "Manufacturer Part") "RC-02K49R9FT") (field (name "Manufacturer") "FH(风华)"))
      (libsource (lib "") (part "RC-02K49R9FT"))
    )
    (comp (ref "R68")
      (value "49.9Ω")
      (fields (field (name "Manufacturer Part") "RC-02K49R9FT") (field (name "Manufacturer") "FH(风华)"))
      (libsource (lib "") (part "RC-02K49R9FT"))
    )
    (comp (ref "R69")
      (value "49.9Ω")
      (fields (field (name "Manufacturer Part") "RC-02K49R9FT") (field (name "Manufacturer") "FH(风华)"))
      (libsource (lib "") (part "RC-02K49R9FT"))
    )
    (comp (ref "R70")
      (value "49.9Ω")
      (fields (field (name "Manufacturer Part") "RC-02K49R9FT") (field (name "Manufacturer") "FH(风华)"))
      (libsource (lib "") (part "RC-02K49R9FT"))
    )
    (comp (ref "R71")
      (value "49.9Ω")
      (fields (field (name "Manufacturer Part") "RC-02K49R9FT") (field (name "Manufacturer") "FH(风华)"))
      (libsource (lib "") (part "RC-02K49R9FT"))
    )
    (comp (ref "R72")
      (value "49.9Ω")
      (fields (field (name "Manufacturer Part") "RC-02K49R9FT") (field (name "Manufacturer") "FH(风华)"))
      (libsource (lib "") (part "RC-02K49R9FT"))
    )
    (comp (ref "R73")
      (value "10kΩ")
      (fields (field (name "Manufacturer Part") "RT0603BRD0710KL") (field (name "Manufacturer") "YAGEO(国巨)"))
      (libsource (lib "") (part "RT0603BRD0710KL"))
    )
    (comp (ref "R74")
      (value "49.9Ω")
      (fields (field (name "Manufacturer Part") "RC-02K49R9FT") (field (name "Manufacturer") "FH(风华)"))
      (libsource (lib "") (part "RC-02K49R9FT"))
    )
    (comp (ref "R75")
      (value "10kΩ")
      (fields (field (name "Manufacturer Part") "RT0603BRD0710KL") (field (name "Manufacturer") "YAGEO(国巨)"))
      (libsource (lib "") (part "RT0603BRD0710KL"))
    )
    (comp (ref "R76")
      (value "10kΩ")
      (fields (field (name "Manufacturer Part") "RT0603BRD0710KL") (field (name "Manufacturer") "YAGEO(国巨)"))
      (libsource (lib "") (part "RT0603BRD0710KL"))
    )
    (comp (ref "R77")
      (value "10kΩ")
      (fields (field (name "Manufacturer Part") "0603WAF1002T5E") (field (name "Manufacturer") "UniOhm"))
      (libsource (lib "") (part "0603WAF1002T5E"))
    )
    (comp (ref "R78")
      (value "10kΩ")
      (fields (field (name "Manufacturer Part") "RT0603BRD0710KL") (field (name "Manufacturer") "YAGEO(国巨)"))
      (libsource (lib "") (part "RT0603BRD0710KL_1"))
    )
    (comp (ref "R79")
      (value "10kΩ")
      (fields (field (name "Manufacturer Part") "RT0603BRD0710KL") (field (name "Manufacturer") "YAGEO(国巨)"))
      (libsource (lib "") (part "RT0603BRD0710KL_1"))
    )
    (comp (ref "U1") (value "MQSocket") (libsource (lib "") (part "MQSocket")))
    (comp (ref "U2")
      (value "INA333AIDGKR")
      (fields (field (name "Manufacturer") "TI(德州仪器)"))
      (libsource (lib "") (part "INA333AIDGKR"))
    )
    (comp (ref "U3")
      (value "INA333AIDGKR")
      (fields (field (name "Manufacturer") "TI(德州仪器)"))
      (libsource (lib "") (part "INA333AIDGKR"))
    )
    (comp (ref "U4")
      (value "LM321DTR(XBLW)")
      (fields (field (name "Manufacturer") "XBLW(芯伯乐)"))
      (libsource (lib "") (part "LM321DTR(XBLW)"))
    )
    (comp (ref "U5")
      (value "LM321DTR(XBLW)")
      (fields (field (name "Manufacturer") "XBLW(芯伯乐)"))
      (libsource (lib "") (part "LM321DTR(XBLW)"))
    )
    (comp (ref "U6")
      (value "MCP4725A0T-E/CH")
      (fields (field (name "Manufacturer") "MICROCHIP(美国微芯)"))
      (libsource (lib "") (part "MCP4725A0T-E/CH"))
    )
    (comp (ref "U7") (value "MQSocket") (libsource (lib "") (part "MQSocket")))
    (comp (ref "U8")
      (value "MCP4725A0T-E/CH")
      (fields (field (name "Manufacturer") "MICROCHIP(美国微芯)"))
      (libsource (lib "") (part "MCP4725A0T-E/CH"))
    )
    (comp (ref "U9")
      (value "INA333AIDGKR")
      (fields (field (name "Manufacturer") "TI(德州仪器)"))
      (libsource (lib "") (part "INA333AIDGKR"))
    )
    (comp (ref "U10")
      (value "LM321DTR(XBLW)")
      (fields (field (name "Manufacturer") "XBLW(芯伯乐)"))
      (libsource (lib "") (part "LM321DTR(XBLW)"))
    )
    (comp (ref "U11")
      (value "MCP4725A0T-E/CH")
      (fields (field (name "Manufacturer") "MICROCHIP(美国微芯)"))
      (libsource (lib "") (part "MCP4725A0T-E/CH"))
    )
    (comp (ref "U12") (value "MQSocket") (libsource (lib "") (part "MQSocket")))
    (comp (ref "U13")
      (value "INA333AIDGKR")
      (fields (field (name "Manufacturer") "TI(德州仪器)"))
      (libsource (lib "") (part "INA333AIDGKR"))
    )
    (comp (ref "U14")
      (value "LM321DTR(XBLW)")
      (fields (field (name "Manufacturer") "XBLW(芯伯乐)"))
      (libsource (lib "") (part "LM321DTR(XBLW)"))
    )
    (comp (ref "U15")
      (value "MCP4725A0T-E/CH")
      (fields (field (name "Manufacturer") "MICROCHIP(美国微芯)"))
      (libsource (lib "") (part "MCP4725A0T-E/CH"))
    )
    (comp (ref "U16") (value "MQSocket") (libsource (lib "") (part "MQSocket")))
    (comp (ref "U17")
      (value "INA333AIDGKR")
      (fields (field (name "Manufacturer") "TI(德州仪器)"))
      (libsource (lib "") (part "INA333AIDGKR"))
    )
    (comp (ref "U18")
      (value "LM321DTR(XBLW)")
      (fields (field (name "Manufacturer") "XBLW(芯伯乐)"))
      (libsource (lib "") (part "LM321DTR(XBLW)"))
    )
    (comp (ref "U19")
      (value "MCP4725A0T-E/CH")
      (fields (field (name "Manufacturer") "MICROCHIP(美国微芯)"))
      (libsource (lib "") (part "MCP4725A0T-E/CH"))
    )
    (comp (ref "U20") (value "MQSocket") (libsource (lib "") (part "MQSocket")))
    (comp (ref "U21")
      (value "INA333AIDGKR")
      (fields (field (name "Manufacturer") "TI(德州仪器)"))
      (libsource (lib "") (part "INA333AIDGKR"))
    )
    (comp (ref "U22")
      (value "LM321DTR(XBLW)")
      (fields (field (name "Manufacturer") "XBLW(芯伯乐)"))
      (libsource (lib "") (part "LM321DTR(XBLW)"))
    )
    (comp (ref "U23")
      (value "MCP4725A0T-E/CH")
      (fields (field (name "Manufacturer") "MICROCHIP(美国微芯)"))
      (libsource (lib "") (part "MCP4725A0T-E/CH"))
    )
    (comp (ref "U24") (value "MQSocket") (libsource (lib "") (part "MQSocket")))
    (comp (ref "U25")
      (value "INA333AIDGKR")
      (fields (field (name "Manufacturer") "TI(德州仪器)"))
      (libsource (lib "") (part "INA333AIDGKR"))
    )
    (comp (ref "U26")
      (value "LM321DTR(XBLW)")
      (fields (field (name "Manufacturer") "XBLW(芯伯乐)"))
      (libsource (lib "") (part "LM321DTR(XBLW)"))
    )
    (comp (ref "U27")
      (value "MCP4725A0T-E/CH")
      (fields (field (name "Manufacturer") "MICROCHIP(美国微芯)"))
      (libsource (lib "") (part "MCP4725A0T-E/CH"))
    )
    (comp (ref "U28") (value "MQSocket") (libsource (lib "") (part "MQSocket")))
    (comp (ref "U29")
      (value "INA333AIDGKR")
      (fields (field (name "Manufacturer") "TI(德州仪器)"))
      (libsource (lib "") (part "INA333AIDGKR"))
    )
    (comp (ref "U30")
      (value "LM321DTR(XBLW)")
      (fields (field (name "Manufacturer") "XBLW(芯伯乐)"))
      (libsource (lib "") (part "LM321DTR(XBLW)"))
    )
    (comp (ref "U31")
      (value "MCP4725A0T-E/CH")
      (fields (field (name "Manufacturer") "MICROCHIP(美国微芯)"))
      (libsource (lib "") (part "MCP4725A0T-E/CH"))
    )
    (comp (ref "U32") (value "MQSocket") (libsource (lib "") (part "MQSocket")))
    (comp (ref "U33")
      (value "TCA9548APWR")
      (fields (field (name "Manufacturer") "TI(德州仪器)"))
      (libsource (lib "") (part "TCA9548APWR"))
    )
    (comp (ref "U34")
      (value "OPA333AIDBVR")
      (fields (field (name "Manufacturer") "TI(德州仪器)"))
      (libsource (lib "") (part "OPA333AIDBVR"))
    )
    (comp (ref "U35")
      (value "ADS1256IDBR")
      (fields (field (name "Manufacturer") "TI(德州仪器)"))
      (libsource (lib "") (part "ADS1256IDBR"))
    )
    (comp (ref "U37")
      (value "LM321DTR(XBLW)")
      (fields (field (name "Manufacturer") "XBLW(芯伯乐)"))
      (libsource (lib "") (part "LM321DTR(XBLW)"))
    )
    (comp (ref "U38")
      (value "ADR03AKSZ-REEL7")
      (fields (field (name "Manufacturer") "ADI(亚德诺)"))
      (libsource (lib "") (part "ADR03AKSZ-REEL7"))
    )
    (comp (ref "U39")
      (value "8MHz")
      (fields (field (name "Manufacturer Part") "3TJ480000NYLBC") (field (name "Manufacturer") "JYJE(晶友嘉)"))
      (libsource (lib "") (part "3TJ480000NYLBC"))
    )
    (comp (ref "C59")
      (value "10uF")
      (fields
        (field (name "Manufacturer Part") "GRM21BR61H106KE43L")
        (field (name "Manufacturer") "muRata(村田)")
      )
      (libsource (lib "") (part "GRM21BR61H106KE43L"))
    )
    (comp (ref "C60")
      (value "10uF")
      (fields
        (field (name "Manufacturer Part") "GRM21BR61H106KE43L")
        (field (name "Manufacturer") "muRata(村田)")
      )
      (libsource (lib "") (part "GRM21BR61H106KE43L"))
    )
    (comp (ref "C61")
      (value "100nF")
      (fields (field (name "Manufacturer Part") "CC0603KRX7R9BB104") (field (name "Manufacturer") "YAGEO"))
      (libsource (lib "") (part "CC0603KRX7R9BB104_1"))
    )
    (comp (ref "C69")
      (value "100nF")
      (fields (field (name "Manufacturer Part") "CC0603KRX7R9BB104") (field (name "Manufacturer") "YAGEO"))
      (libsource (lib "") (part "CC0603KRX7R9BB104"))
    )
    (comp (ref "C70")
      (value "33pF")
      (fields
        (field (name "Manufacturer Part") "CL10C330JB8NNNC")
        (field (name "Manufacturer") "SAMSUNG(三星)")
      )
      (libsource (lib "") (part "CL10C330JB8NNNC"))
    )
    (comp (ref "C71")
      (value "100nF")
      (fields (field (name "Manufacturer Part") "CC0603KRX7R9BB104") (field (name "Manufacturer") "YAGEO"))
      (libsource (lib "") (part "CC0603KRX7R9BB104_1"))
    )
    (comp (ref "C72")
      (value "33uF")
      (fields (field (name "Manufacturer Part") "C2012X5R1A336MTJ00E") (field (name "Manufacturer") "TDK"))
      (libsource (lib "") (part "C2012X5R1A336MTJ00E"))
    )
    (comp (ref "C73")
      (value "33uF")
      (fields (field (name "Manufacturer Part") "C2012X5R1A336MTJ00E") (field (name "Manufacturer") "TDK"))
      (libsource (lib "") (part "C2012X5R1A336MTJ00E"))
    )
    (comp (ref "C74")
      (value "10uF")
      (fields
        (field (name "Manufacturer Part") "GRM21BR61H106KE43L")
        (field (name "Manufacturer") "muRata(村田)")
      )
      (libsource (lib "") (part "GRM21BR61H106KE43L"))
    )
    (comp (ref "C75")
      (value "10uF")
      (fields
        (field (name "Manufacturer Part") "GRM21BR61H106KE43L")
        (field (name "Manufacturer") "muRata(村田)")
      )
      (libsource (lib "") (part "GRM21BR61H106KE43L"))
    )
    (comp (ref "C76")
      (value "100nF")
      (fields (field (name "Manufacturer Part") "CC0603KRX7R9BB104") (field (name "Manufacturer") "YAGEO"))
      (libsource (lib "") (part "CC0603KRX7R9BB104"))
    )
    (comp (ref "C77")
      (value "2.2uF")
      (fields
        (field (name "Manufacturer Part") "CL10A225KO8NNNC")
        (field (name "Manufacturer") "SAMSUNG(三星)")
      )
      (libsource (lib "") (part "CL10A225KO8NNNC"))
    )
    (comp (ref "C78")
      (value "22uF")
      (fields
        (field (name "Manufacturer Part") "CL10A226MQ8NRNC")
        (field (name "Manufacturer") "SAMSUNG(三星)")
      )
      (libsource (lib "") (part "CL10A226MQ8NRNC"))
    )
    (comp (ref "C79")
      (value "22uF")
      (fields
        (field (name "Manufacturer Part") "CL10A226MQ8NRNC")
        (field (name "Manufacturer") "SAMSUNG(三星)")
      )
      (libsource (lib "") (part "CL10A226MQ8NRNC"))
    )
    (comp (ref "C80")
      (value "22uF")
      (fields
        (field (name "Manufacturer Part") "CL10A226MQ8NRNC")
        (field (name "Manufacturer") "SAMSUNG(三星)")
      )
      (libsource (lib "") (part "CL10A226MQ8NRNC"))
    )
    (comp (ref "C81")
      (value "1uF")
      (fields
        (field (name "Manufacturer Part") "CL10A105KB8NNNC")
        (field (name "Manufacturer") "SAMSUNG(三星)")
      )
      (libsource (lib "") (part "CL10A105KB8NNNC"))
    )
    (comp (ref "C82")
      (value "47nF")
      (fields
        (field (name "Manufacturer Part") "CL10B473KB8NNNC")
        (field (name "Manufacturer") "SAMSUNG(三星)")
      )
      (libsource (lib "") (part "CL10B473KB8NNNC"))
    )
    (comp (ref "C83")
      (value "4.7nF")
      (fields (field (name "Manufacturer Part") "0603B472K500NT") (field (name "Manufacturer") "FH(风华)"))
      (libsource (lib "") (part "0603B472K500NT"))
    )
    (comp (ref "C84")
      (value "47nF")
      (fields
        (field (name "Manufacturer Part") "CL10B473KB8NNNC")
        (field (name "Manufacturer") "SAMSUNG(三星)")
      )
      (libsource (lib "") (part "CL10B473KB8NNNC_1"))
    )
    (comp (ref "C85")
      (value "10uF")
      (fields (field (name "Manufacturer Part") "CL10A106KP8NNNC") (field (name "Manufacturer") "SAMSUNG"))
      (libsource (lib "") (part "CL10A106KP8NNNC"))
    )
    (comp (ref "C86")
      (value "100nF")
      (fields
        (field (name "Manufacturer Part") "CC0603KRX7R9BB104")
        (field (name "Manufacturer") "YAGEO(国巨)")
      )
      (libsource (lib "") (part "CC0603KRX7R9BB104_1"))
    )
    (comp (ref "C87")
      (value "100nF")
      (fields
        (field (name "Manufacturer Part") "CL05B104KO5NNNC")
        (field (name "Manufacturer") "SAMSUNG(三星)")
      )
      (libsource (lib "") (part "CL05B104KO5NNNC"))
    )
    (comp (ref "C88")
      (value "10uF")
      (fields
        (field (name "Manufacturer Part") "CL10A106KP8NNNC")
        (field (name "Manufacturer") "SAMSUNG(三星)")
      )
      (libsource (lib "") (part "CL10A106KP8NNNC"))
    )
    (comp (ref "C89")
      (value "100nF")
      (fields
        (field (name "Manufacturer Part") "CC0603KRX7R9BB104")
        (field (name "Manufacturer") "YAGEO(国巨)")
      )
      (libsource (lib "") (part "CC0603KRX7R9BB104_1"))
    )
    (comp (ref "C90")
      (value "100nF")
      (fields (field (name "Manufacturer Part") "CC0603KRX7R9BB104") (field (name "Manufacturer") "YAGEO"))
      (libsource (lib "") (part "CC0603KRX7R9BB104_1"))
    )
    (comp (ref "C91")
      (value "100nF")
      (fields (field (name "Manufacturer Part") "CC0603KRX7R9BB104") (field (name "Manufacturer") "YAGEO"))
      (libsource (lib "") (part "CC0603KRX7R9BB104_1"))
    )
    (comp (ref "C92")
      (value "100nF")
      (fields (field (name "Manufacturer Part") "CC0603KRX7R9BB104") (field (name "Manufacturer") "YAGEO"))
      (libsource (lib "") (part "CC0603KRX7R9BB104_1"))
    )
    (comp (ref "C93")
      (value "10uF")
      (fields (field (name "Manufacturer Part") "CL31A106KBHNNNE") (field (name "Manufacturer") "SAMSUNG"))
      (libsource (lib "") (part "CL31A106KBHNNNE"))
    )
    (comp (ref "C94")
      (value "10uF")
      (fields
        (field (name "Manufacturer Part") "GRM21BR61H106KE43L")
        (field (name "Manufacturer") "muRata(村田)")
      )
      (libsource (lib "") (part "GRM21BR61H106KE43L"))
    )
    (comp (ref "C95")
      (value "22uF")
      (fields
        (field (name "Manufacturer Part") "CL10A226MQ8NRNC")
        (field (name "Manufacturer") "SAMSUNG(三星)")
      )
      (libsource (lib "") (part "CL10A226MQ8NRNC"))
    )
    (comp (ref "C96")
      (value "22uF")
      (fields
        (field (name "Manufacturer Part") "CL10A226MQ8NRNC")
        (field (name "Manufacturer") "SAMSUNG(三星)")
      )
      (libsource (lib "") (part "CL10A226MQ8NRNC"))
    )
    (comp (ref "C97")
      (value "22uF")
      (fields
        (field (name "Manufacturer Part") "CL10A226MQ8NRNC")
        (field (name "Manufacturer") "SAMSUNG(三星)")
      )
      (libsource (lib "") (part "CL10A226MQ8NRNC"))
    )
    (comp (ref "C98")
      (value "100nF")
      (fields (field (name "Manufacturer Part") "CC0603KRX7R9BB104") (field (name "Manufacturer") "YAGEO"))
      (libsource (lib "") (part "CC0603KRX7R9BB104_1"))
    )
    (comp (ref "C99")
      (value "100nF")
      (fields (field (name "Manufacturer Part") "CC0603KRX7R9BB104") (field (name "Manufacturer") "YAGEO"))
      (libsource (lib "") (part "CC0603KRX7R9BB104_1"))
    )
    (comp (ref "C100")
      (value "100nF")
      (fields (field (name "Manufacturer Part") "CC0603KRX7R9BB104") (field (name "Manufacturer") "YAGEO"))
      (libsource (lib "") (part "CC0603KRX7R9BB104_1"))
    )
    (comp (ref "C101")
      (value "22uF")
      (fields
        (field (name "Manufacturer Part") "CL10A226MQ8NRNC")
        (field (name "Manufacturer") "SAMSUNG(三星)")
      )
      (libsource (lib "") (part "CL10A226MQ8NRNC"))
    )
    (comp (ref "CN1")
      (value "XH-2A-black")
      (fields (field (name "Manufacturer Part") "XH-2A黑色") (field (name "Manufacturer") "BOOMELE(博穆精密)"))
      (libsource (lib "") (part "XH-2A-black_1"))
    )
    (comp (ref "CN2")
      (value "VIN")
      (fields (field (name "Manufacturer Part") "XH-2A黑色") (field (name "Manufacturer") "BOOMELE(博穆精密)"))
      (libsource (lib "") (part "XH-2A-black"))
    )
    (comp (ref "CN3")
      (value "XH-2A-black")
      (fields (field (name "Manufacturer Part") "XH-2A黑色") (field (name "Manufacturer") "BOOMELE(博穆精密)"))
      (libsource (lib "") (part "XH-2A-black_1"))
    )
    (comp (ref "D1")
      (value "SMBJ33A")
      (fields (field (name "Manufacturer") "RUILON(瑞隆源)"))
      (libsource (lib "") (part "SMBJ33A"))
    )
    (comp (ref "D2")
      (value "LBZT52C12T1G")
      (fields (field (name "Manufacturer") "LRC(乐山无线电)"))
      (libsource (lib "") (part "LBZT52C12T1G"))
    )
    (comp (ref "D3")
      (value "BAT54C")
      (fields (field (name "Manufacturer") "CJ(江苏长电/长晶)"))
      (libsource (lib "") (part "BAT54C"))
    )
    (comp (ref "D4")
      (value "LESD5D5.0CT1G_C5199850")
      (fields (field (name "Manufacturer Part") "LESD5D5.0CT1G") (field (name "Manufacturer") "UMW(友台半导体)"))
      (libsource (lib "") (part "LESD5D5.0CT1G_C5199850"))
    )
    (comp (ref "D5")
      (value "LESD5D5.0CT1G_C5199850")
      (fields (field (name "Manufacturer Part") "LESD5D5.0CT1G") (field (name "Manufacturer") "UMW(友台半导体)"))
      (libsource (lib "") (part "LESD5D5.0CT1G_C5199850"))
    )
    (comp (ref "D6")
      (value "SM712")
      (fields (field (name "Manufacturer") "DOWO(东沃)"))
      (libsource (lib "") (part "SM712_C293966"))
    )
    (comp (ref "D7")
      (value "SS54_C22452")
      (fields (field (name "Manufacturer Part") "SS54") (field (name "Manufacturer") "MDD(辰达半导体)"))
      (libsource (lib "") (part "SS54_C22452"))
    )
    (comp (ref "D8")
      (value "SS54_C22452")
      (fields (field (name "Manufacturer Part") "SS54") (field (name "Manufacturer") "MDD(辰达半导体)"))
      (libsource (lib "") (part "SS54_C22452"))
    )
    (comp (ref "D9")
      (value "SS54_C22452")
      (fields (field (name "Manufacturer Part") "SS54") (field (name "Manufacturer") "MDD(辰达半导体)"))
      (libsource (lib "") (part "SS54_C22452"))
    )
    (comp (ref "F1")
      (value "MINISMDC260F/16")
      (fields
        (field (name "Manufacturer Part") "MINISMDC260F/16-2")
        (field (name "Manufacturer") "Littelfuse(美国力特)")
      )
      (libsource (lib "") (part "MINISMDC260F/16"))
    )
    (comp (ref "G$1") (value "UFL") (libsource (lib "") (part "UFL")))
    (comp (ref "J1") (value "VIN") (libsource (lib "") (part "HDR-M-2.54_2x3")))
    (comp (ref "J2") (value "ALARM") (libsource (lib "") (part "HDR-M-2.54_1x4")))
    (comp (ref "L2")
      (value "2.2uH")
      (fields (field (name "Manufacturer Part") "SMDRH105R-2R2NT") (field (name "Manufacturer") "SXN(顺翔诺)"))
      (libsource (lib "") (part "SMDRH105R-2R2NT"))
    )
    (comp (ref "L3")
      (value "2.2uH")
      (fields (field (name "Manufacturer Part") "ANR3015T2R2M") (field (name "Manufacturer") "APV(爱普微)"))
      (libsource (lib "") (part "ANR3015T2R2M"))
    )
    (comp (ref "LED1")
      (value "19-217/BHC-ZL1M2RY/3T")
      (fields (field (name "Manufacturer") "EVERLIGHT"))
      (libsource (lib "") (part "19-217/BHC-ZL1M2RY/3T"))
    )
    (comp (ref "Q1")
      (value "UMH3NTN")
      (fields (field (name "Manufacturer") "ROHM(罗姆)"))
      (libsource (lib "") (part "UMH3NTN"))
    )
    (comp (ref "Q3")
      (value "SI7465DP-T1-GE3")
      (fields (field (name "Manufacturer") "VISHAY(威世)"))
      (libsource (lib "") (part "SI7465DP-T1-GE3"))
    )
    (comp (ref "R80")
      (value "10kΩ")
      (fields (field (name "Manufacturer Part") "0603WAF1002T5E") (field (name "Manufacturer") "UniOhm"))
      (libsource (lib "") (part "0603WAF1002T5E_2"))
    )
    (comp (ref "R81")
      (value "100kΩ")
      (fields
        (field (name "Manufacturer Part") "0603WAF1003T5E")
        (field (name "Manufacturer") "UNI-ROYAL(厚声)")
      )
      (libsource (lib "") (part "0603WAF1003T5E"))
    )
    (comp (ref "R82")
      (value "100kΩ")
      (fields
        (field (name "Manufacturer Part") "0603WAF1003T5E")
        (field (name "Manufacturer") "UNI-ROYAL(厚声)")
      )
      (libsource (lib "") (part "0603WAF1003T5E"))
    )
    (comp (ref "R83")
      (value "200kΩ")
      (fields
        (field (name "Manufacturer Part") "0603WAF2003T5E")
        (field (name "Manufacturer") "UNI-ROYAL(厚声)")
      )
      (libsource (lib "") (part "0603WAF2003T5E"))
    )
    (comp (ref "R84")
      (value "100kΩ")
      (fields
        (field (name "Manufacturer Part") "0603WAF1003T5E")
        (field (name "Manufacturer") "UNI-ROYAL(厚声)")
      )
      (libsource (lib "") (part "0603WAF1003T5E_1"))
    )
    (comp (ref "R85")
      (value "100kΩ")
      (fields
        (field (name "Manufacturer Part") "0603WAF1003T5E")
        (field (name "Manufacturer") "UNI-ROYAL(厚声)")
      )
      (libsource (lib "") (part "0603WAF1003T5E"))
    )
    (comp (ref "R86")
      (value "19.1kΩ")
      (fields
        (field (name "Manufacturer Part") "0603WAF1912T5E")
        (field (name "Manufacturer") "UNI-ROYAL(厚声)")
      )
      (libsource (lib "") (part "0603WAF1912T5E"))
    )
    (comp (ref "R87")
      (value "1kΩ")
      (fields
        (field (name "Manufacturer Part") "0603WAF1001T5E")
        (field (name "Manufacturer") "UNI-ROYAL(厚声)")
      )
      (libsource (lib "") (part "0603WAF1001T5E"))
    )
    (comp (ref "R88")
      (value "255kΩ")
      (fields
        (field (name "Manufacturer Part") "0603WAF2553T5E")
        (field (name "Manufacturer") "UNI-ROYAL(厚声)")
      )
      (libsource (lib "") (part "0603WAF2553T5E"))
    )
    (comp (ref "R89")
      (value "56kΩ")
      (fields
        (field (name "Manufacturer Part") "0603WAF5602T5E")
        (field (name "Manufacturer") "UNI-ROYAL(厚声)")
      )
      (libsource (lib "") (part "0603WAF5602T5E"))
    )
    (comp (ref "R90")
      (value "189k")
      (fields (field (name "Manufacturer Part") "RT0603BRD07189KL") (field (name "Manufacturer") "YAGEO(国巨)"))
      (libsource (lib "") (part "RT0603BRD07189KL"))
    )
    (comp (ref "R91")
      (value "100kΩ")
      (fields
        (field (name "Manufacturer Part") "0603WAF1003T5E")
        (field (name "Manufacturer") "UNI-ROYAL(厚声)")
      )
      (libsource (lib "") (part "0603WAF1003T5E_2"))
    )
    (comp (ref "R92")
      (value "33kΩ")
      (fields
        (field (name "Manufacturer Part") "0603WAF3302T5E")
        (field (name "Manufacturer") "UNI-ROYAL(厚声)")
      )
      (libsource (lib "") (part "0603WAF3302T5E"))
    )
    (comp (ref "R93")
      (value "2kΩ")
      (fields
        (field (name "Manufacturer Part") "0603WAF2001T5E")
        (field (name "Manufacturer") "UNI-ROYAL(厚声)")
      )
      (libsource (lib "") (part "0603WAF2001T5E"))
    )
    (comp (ref "R94")
      (value "10kΩ")
      (fields (field (name "Manufacturer Part") "0603WAF1002T5E") (field (name "Manufacturer") "UniOhm"))
      (libsource (lib "") (part "0603WAF1002T5E"))
    )
    (comp (ref "R95")
      (value "10kΩ")
      (fields (field (name "Manufacturer Part") "0603WAF1002T5E") (field (name "Manufacturer") "UniOhm"))
      (libsource (lib "") (part "0603WAF1002T5E"))
    )
    (comp (ref "R96")
      (value "470Ω")
      (fields
        (field (name "Manufacturer Part") "0603WAF4700T5E")
        (field (name "Manufacturer") "UNI-ROYAL(厚声)")
      )
      (libsource (lib "") (part "0603WAF4700T5E"))
    )
    (comp (ref "R97")
      (value "10kΩ")
      (fields (field (name "Manufacturer Part") "0603WAF1002T5E") (field (name "Manufacturer") "UniOhm"))
      (libsource (lib "") (part "0603WAF1002T5E"))
    )
    (comp (ref "R98")
      (value "10kΩ")
      (fields (field (name "Manufacturer Part") "0603WAF1002T5E") (field (name "Manufacturer") "UniOhm"))
      (libsource (lib "") (part "0603WAF1002T5E"))
    )
    (comp (ref "R99")
      (value "100kΩ")
      (fields
        (field (name "Manufacturer Part") "0603WAF1003T5E")
        (field (name "Manufacturer") "UNI-ROYAL(厚声)")
      )
      (libsource (lib "") (part "0603WAF1003T5E_2"))
    )
    (comp (ref "R100")
      (value "0Ω")
      (fields
        (field (name "Manufacturer Part") "0603WAF0000T5E")
        (field (name "Manufacturer") "UNI-ROYAL(厚声)")
      )
      (libsource (lib "") (part "0603WAF0000T5E"))
    )
    (comp (ref "R104")
      (value "100kΩ")
      (fields
        (field (name "Manufacturer Part") "0603WAF1003T5E")
        (field (name "Manufacturer") "UNI-ROYAL(厚声)")
      )
      (libsource (lib "") (part "0603WAF1003T5E_3"))
    )
    (comp (ref "R105")
      (value "10kΩ")
      (fields (field (name "Manufacturer Part") "0603WAF1002T5E") (field (name "Manufacturer") "UniOhm"))
      (libsource (lib "") (part "0603WAF1002T5E_1"))
    )
    (comp (ref "R106")
      (value "10kΩ")
      (fields (field (name "Manufacturer Part") "0603WAF1002T5E") (field (name "Manufacturer") "UniOhm"))
      (libsource (lib "") (part "0603WAF1002T5E_1"))
    )
    (comp (ref "R107")
      (value "10kΩ")
      (fields (field (name "Manufacturer Part") "0603WAF1002T5E") (field (name "Manufacturer") "UniOhm"))
      (libsource (lib "") (part "0603WAF1002T5E"))
    )
    (comp (ref "SW1")
      (value "SKQYAAE010")
      (fields (field (name "Manufacturer") "ALPSALPINE(阿尔卑斯阿尔派)"))
      (libsource (lib "") (part "SKQYAAE010"))
    )
    (comp (ref "U36")
      (value "LMR51450SDRRR")
      (fields (field (name "Manufacturer") "TI(德州仪器)"))
      (libsource (lib "") (part "LMR51450SDRRR"))
    )
    (comp (ref "U40")
      (value "4.7uH")
      (fields (field (name "Manufacturer Part") "GSSM06304R7M2AU") (field (name "Manufacturer") "ABC(千如)"))
      (libsource (lib "") (part "GSSM06304R7M2AU"))
    )
    (comp (ref "U41")
      (value "TPS61088RHLR")
      (fields (field (name "Manufacturer") "TI(德州仪器)"))
      (libsource (lib "") (part "TPS61088RHLR"))
    )
    (comp (ref "U42")
      (value "TPS7A0233DBVR")
      (fields (field (name "Manufacturer") "TI(德州仪器)"))
      (libsource (lib "") (part "TPS7A0233DBVR"))
    )
    (comp (ref "U43")
      (value "TPS62162DSG")
      (fields (field (name "Manufacturer Part") "TPS62162DSGR") (field (name "Manufacturer") "TI(德州仪器)"))
      (libsource (lib "") (part "TPS62162DSG"))
    )
    (comp (ref "U44")
      (value "ULN2003G-P16-R")
      (fields (field (name "Manufacturer") "UTC(友顺)"))
      (libsource (lib "") (part "ULN2003G-P16-R"))
    )
    (comp (ref "U45")
      (value "E22-900MM22S")
      (fields (field (name "Manufacturer") "EBYTE(亿佰特)"))
      (libsource (lib "") (part "E22-900MM22S"))
    )
    (comp (ref "U46")
      (value "TPL5010")
      (fields (field (name "Manufacturer Part") "TPL5010DDCR") (field (name "Manufacturer") "TI(德州仪器)"))
      (libsource (lib "") (part "TPL5010DDCR"))
    )
    (comp (ref "U47")
      (value "THVD1410DR")
      (fields (field (name "Manufacturer") "TI(德州仪器)"))
      (libsource (lib "") (part "THVD1410DR"))
    )
    (comp (ref "U48")
      (value "CH340C")
      (fields (field (name "Manufacturer") "WCH(南京沁恒)"))
      (libsource (lib "") (part "CH340C"))
    )
    (comp (ref "U49")
      (value "ESP32-S3-WROOM-1U-N16R8")
      (fields (field (name "Manufacturer") "ESPRESSIF(乐鑫)"))
      (libsource (lib "") (part "ESP32-S3-WROOM-1U-N16R8"))
    )
    (comp (ref "U50") (value "casingAlGasLeak") (libsource (lib "") (part "casingAlGasLeak")))
    (comp (ref "U51")
      (value "SN74AUP1G74DCUR")
      (fields (field (name "Manufacturer") "TI(德州仪器)"))
      (libsource (lib "") (part "SN74AUP1G74DCUR"))
    )
    (comp (ref "U52")
      (value "SN74LVC1G04DCKR")
      (fields (field (name "Manufacturer") "TI(德州仪器)"))
      (libsource (lib "") (part "SN74LVC1G04DCKR"))
    )
    (comp (ref "USB1")
      (value "U-D-M5DD-W-1")
      (fields (field (name "Manufacturer") "韩国韩荣"))
      (libsource (lib "") (part "U-D-M5DD-W-1"))
    )
  )
  (nets
    (net (code "1") (name "+5V") (class "Default")
      (node (ref "C65") (pin "2") (pinfunction "2_2") (pintype "unspecified"))
      (node (ref "C94") (pin "2") (pinfunction "2_2") (pintype "unspecified"))
      (node (ref "CN1") (pin "1") (pinfunction "1_1") (pintype "unspecified"))
      (node (ref "D7") (pin "2") (pinfunction "K_2") (pintype "unspecified"))
      (node (ref "D8") (pin "2") (pinfunction "K_2") (pintype "unspecified"))
      (node (ref "D9") (pin "2") (pinfunction "K_2") (pintype "unspecified"))
      (node (ref "J2") (pin "1") (pinfunction "1_1") (pintype "unspecified"))
      (node (ref "L1") (pin "2") (pinfunction "2_2") (pintype "unspecified"))
      (node (ref "R77") (pin "2") (pinfunction "2_2") (pintype "input"))
      (node (ref "U1") (pin "2") (pinfunction "H_2") (pintype "unspecified"))
      (node (ref "U12") (pin "2") (pinfunction "H_2") (pintype "unspecified"))
      (node (ref "U16") (pin "2") (pinfunction "H_2") (pintype "unspecified"))
      (node (ref "U20") (pin "2") (pinfunction "H_2") (pintype "unspecified"))
      (node (ref "U24") (pin "2") (pinfunction "H_2") (pintype "unspecified"))
      (node (ref "U28") (pin "2") (pinfunction "H_2") (pintype "unspecified"))
      (node (ref "U32") (pin "2") (pinfunction "H_2") (pintype "unspecified"))
      (node (ref "U33") (pin "1") (pinfunction "A0_1") (pintype "unspecified"))
      (node (ref "U33") (pin "24") (pinfunction "VCC_24") (pintype "unspecified"))
      (node (ref "U43") (pin "2") (pinfunction "VIN_2") (pintype "passive"))
      (node (ref "U43") (pin "3") (pinfunction "EN_3") (pintype "unspecified"))
      (node (ref "U44") (pin "9") (pinfunction "COM_9") (pintype "unspecified"))
      (node (ref "U7") (pin "2") (pinfunction "H_2") (pintype "unspecified"))
    )
    (net (code "2") (name "+5VA") (class "Default")
      (node (ref "C11") (pin "2") (pinfunction "2_2") (pintype "unspecified"))
      (node (ref "C12") (pin "2") (pinfunction "2_2") (pintype "unspecified"))
      (node (ref "C13") (pin "2") (pinfunction "2_2") (pintype "unspecified"))
      (node (ref "C14") (pin "2") (pinfunction "2_2") (pintype "unspecified"))
      (node (ref "C15") (pin "2") (pinfunction "2_2") (pintype "unspecified"))
      (node (ref "C18") (pin "2") (pinfunction "2_2") (pintype "unspecified"))
      (node (ref "C19") (pin "2") (pinfunction "2_2") (pintype "unspecified"))
      (node (ref "C2") (pin "2") (pinfunction "2_2") (pintype "unspecified"))
      (node (ref "C20") (pin "2") (pinfunction "2_2") (pintype "unspecified"))
      (node (ref "C23") (pin "2") (pinfunction "2_2") (pintype "unspecified"))
      (node (ref "C24") (pin "2") (pinfunction "2_2") (pintype "unspecified"))
      (node (ref "C25") (pin "2") (pinfunction "2_2") (pintype "unspecified"))
      (node (ref "C28") (pin "2") (pinfunction "2_2") (pintype "unspecified"))
      (node (ref "C29") (pin "2") (pinfunction "2_2") (pintype "unspecified"))
      (node (ref "C30") (pin "2") (pinfunction "2_2") (pintype "unspecified"))
      (node (ref "C33") (pin "2") (pinfunction "2_2") (pintype "unspecified"))
      (node (ref "C34") (pin "2") (pinfunction "2_2") (pintype "unspecified"))
      (node (ref "C35") (pin "2") (pinfunction "2_2") (pintype "unspecified"))
      (node (ref "C38") (pin "2") (pinfunction "2_2") (pintype "unspecified"))
      (node (ref "C39") (pin "2") (pinfunction "2_2") (pintype "unspecified"))
      (node (ref "C40") (pin "2") (pinfunction "2_2") (pintype "unspecified"))
      (node (ref "C46") (pin "2") (pinfunction "2_2") (pintype "unspecified"))
      (node (ref "C52") (pin "2") (pinfunction "2_2") (pintype "unspecified"))
      (node (ref "C6") (pin "2") (pinfunction "2_2") (pintype "unspecified"))
      (node (ref "C62") (pin "2") (pinfunction "2_2") (pintype "unspecified"))
      (node (ref "C63") (pin "1") (pinfunction "1_1") (pintype "input"))
      (node (ref "C64") (pin "2") (pinfunction "2_2") (pintype "unspecified"))
      (node (ref "C7") (pin "2") (pinfunction "2_2") (pintype "unspecified"))
      (node (ref "C8") (pin "2") (pinfunction "2_2") (pintype "unspecified"))
      (node (ref "L1") (pin "1") (pinfunction "1_1") (pintype "unspecified"))
      (node (ref "R15") (pin "1") (pinfunction "1_1") (pintype "input"))
      (node (ref "R16") (pin "1") (pinfunction "1_1") (pintype "input"))
      (node (ref "R17") (pin "2") (pinfunction "2_2") (pintype "input"))
      (node (ref "R22") (pin "1") (pinfunction "1_1") (pintype "input"))
      (node (ref "R23") (pin "1") (pinfunction "1_1") (pintype "input"))
      (node (ref "R26") (pin "1") (pinfunction "1_1") (pintype "input"))
      (node (ref "R27") (pin "1") (pinfunction "1_1") (pintype "input"))
      (node (ref "R28") (pin "2") (pinfunction "2_2") (pintype "input"))
      (node (ref "R3") (pin "1") (pinfunction "1_1") (pintype "input"))
      (node (ref "R34") (pin "1") (pinfunction "1_1") (pintype "input"))
      (node (ref "R35") (pin "1") (pinfunction "1_1") (pintype "input"))
      (node (ref "R36") (pin "2") (pinfunction "2_2") (pintype "input"))
      (node (ref "R4") (pin "1") (pinfunction "1_1") (pintype "input"))
      (node (ref "R42") (pin "1") (pinfunction "1_1") (pintype "input"))
      (node (ref "R43") (pin "1") (pinfunction "1_1") (pintype "input"))
      (node (ref "R44") (pin "2") (pinfunction "2_2") (pintype "input"))
      (node (ref "R5") (pin "2") (pinfunction "2_2") (pintype "input"))
      (node (ref "R50") (pin "1") (pinfunction "1_1") (pintype "input"))
      (node (ref "R51") (pin "1") (pinfunction "1_1") (pintype "input"))
      (node (ref "R52") (pin "2") (pinfunction "2_2") (pintype "input"))
      (node (ref "R58") (pin "1") (pinfunction "1_1") (pintype "input"))
      (node (ref "R59") (pin "1") (pinfunction "1_1") (pintype "input"))
      (node (ref "R60") (pin "2") (pinfunction "2_2") (pintype "input"))
      (node (ref "R7") (pin "2") (pinfunction "2_2") (pintype "input"))
      (node (ref "R78") (pin "2") (pinfunction "2_2") (pintype "input"))
      (node (ref "U10") (pin "5") (pinfunction "V+_5") (pintype "passive"))
      (node (ref "U11") (pin "3") (pinfunction "VDD_3") (pintype "unspecified"))
      (node (ref "U13") (pin "7") (pinfunction "V+_7") (pintype "unspecified"))
      (node (ref "U14") (pin "5") (pinfunction "V+_5") (pintype "passive"))
      (node (ref "U15") (pin "3") (pinfunction "VDD_3") (pintype "unspecified"))
      (node (ref "U17") (pin "7") (pinfunction "V+_7") (pintype "unspecified"))
      (node (ref "U18") (pin "5") (pinfunction "V+_5") (pintype "passive"))
      (node (ref "U19") (pin "3") (pinfunction "VDD_3") (pintype "unspecified"))
      (node (ref "U2") (pin "7") (pinfunction "V+_7") (pintype "unspecified"))
      (node (ref "U21") (pin "7") (pinfunction "V+_7") (pintype "unspecified"))
      (node (ref "U22") (pin "5") (pinfunction "V+_5") (pintype "passive"))
      (node (ref "U23") (pin "3") (pinfunction "VDD_3") (pintype "unspecified"))
      (node (ref "U25") (pin "7") (pinfunction "V+_7") (pintype "unspecified"))
      (node (ref "U26") (pin "5") (pinfunction "V+_5") (pintype "passive"))
      (node (ref "U27") (pin "3") (pinfunction "VDD_3") (pintype "unspecified"))
      (node (ref "U29") (pin "7") (pinfunction "V+_7") (pintype "unspecified"))
      (node (ref "U3") (pin "7") (pinfunction "V+_7") (pintype "unspecified"))
      (node (ref "U30") (pin "5") (pinfunction "V+_5") (pintype "passive"))
      (node (ref "U31") (pin "3") (pinfunction "VDD_3") (pintype "unspecified"))
      (node (ref "U34") (pin "5") (pinfunction "V+_5") (pintype "passive"))
      (node (ref "U35") (pin "1") (pinfunction "AVDD_1") (pintype "passive"))
      (node (ref "U37") (pin "5") (pinfunction "V+_5") (pintype "passive"))
      (node (ref "U38") (pin "3") (pinfunction "VIN_3") (pintype "unspecified"))
      (node (ref "U4") (pin "5") (pinfunction "V+_5") (pintype "passive"))
      (node (ref "U5") (pin "5") (pinfunction "V+_5") (pintype "passive"))
      (node (ref "U6") (pin "3") (pinfunction "VDD_3") (pintype "unspecified"))
      (node (ref "U8") (pin "3") (pinfunction "VDD_3") (pintype "unspecified"))
      (node (ref "U9") (pin "7") (pinfunction "V+_7") (pintype "unspecified"))
    )
    (net (code "3") (name "3V3AON") (class "Default")
      (node (ref "C100") (pin "2") (pinfunction "2_2") (pintype "unspecified"))
      (node (ref "C101") (pin "2") (pinfunction "2_2") (pintype "unspecified"))
      (node (ref "C98") (pin "2") (pinfunction "2_2") (pintype "unspecified"))
      (node (ref "C99") (pin "2") (pinfunction "2_2") (pintype "unspecified"))
      (node (ref "R106") (pin "1") (pinfunction "1_1") (pintype "input"))
      (node (ref "R107") (pin "2") (pinfunction "2_2") (pintype "input"))
      (node (ref "U42") (pin "5") (pinfunction "OUT_5") (pintype "unspecified"))
      (node (ref "U46") (pin "1") (pinfunction "VDD_1") (pintype "unspecified"))
      (node (ref "U51") (pin "8") (pinfunction "VCC_8") (pintype "unspecified"))
      (node (ref "U52") (pin "5") (pinfunction "VCC_5") (pintype "unspecified"))
    )
    (net (code "4") (name "5VBUCK") (class "Default")
      (node (ref "C72") (pin "2") (pinfunction "2_2") (pintype "unspecified"))
      (node (ref "C73") (pin "2") (pinfunction "2_2") (pintype "unspecified"))
      (node (ref "D3") (pin "2") (pinfunction "A2_2") (pintype "unspecified"))
      (node (ref "D8") (pin "1") (pinfunction "A_1") (pintype "unspecified"))
      (node (ref "R85") (pin "2") (pinfunction "2_2") (pintype "input"))
      (node (ref "R87") (pin "2") (pinfunction "2_2") (pintype "input"))
      (node (ref "U40") (pin "2") (pinfunction "2_2") (pintype "unspecified"))
    )
    (net (code "5") (name "5VEXT") (class "Default")
      (node (ref "D7") (pin "1") (pinfunction "A_1") (pintype "unspecified"))
      (node (ref "J1") (pin "4") (pinfunction "4_4") (pintype "input"))
    )
    (net (code "6") (name "A") (class "Default")
      (node (ref "CN3") (pin "2") (pinfunction "2_2") (pintype "unspecified"))
      (node (ref "D6") (pin "2") (pinfunction "2_2") (pintype "unspecified"))
      (node (ref "U47") (pin "6") (pinfunction "A_6") (pintype "unspecified"))
    )
    (net (code "7") (name "AGND") (class "Default")
      (node (ref "C67") (pin "2") (pinfunction "2_2") (pintype "unspecified"))
      (node (ref "C68") (pin "2") (pinfunction "2_2") (pintype "unspecified"))
      (node (ref "R10") (pin "1") (pinfunction "1_1") (pintype "input"))
      (node (ref "R20") (pin "1") (pinfunction "1_1") (pintype "input"))
      (node (ref "R31") (pin "1") (pinfunction "1_1") (pintype "input"))
      (node (ref "R39") (pin "1") (pinfunction "1_1") (pintype "input"))
      (node (ref "R47") (pin "1") (pinfunction "1_1") (pintype "input"))
      (node (ref "R55") (pin "1") (pinfunction "1_1") (pintype "input"))
      (node (ref "R6") (pin "1") (pinfunction "1_1") (pintype "input"))
      (node (ref "R63") (pin "1") (pinfunction "1_1") (pintype "input"))
      (node (ref "U1") (pin "1") (pinfunction "A_1") (pintype "unspecified"))
      (node (ref "U1") (pin "3") (pinfunction "A_3") (pintype "unspecified"))
      (node (ref "U12") (pin "1") (pinfunction "A_1") (pintype "unspecified"))
      (node (ref "U12") (pin "3") (pinfunction "A_3") (pintype "unspecified"))
      (node (ref "U16") (pin "1") (pinfunction "A_1") (pintype "unspecified"))
      (node (ref "U16") (pin "3") (pinfunction "A_3") (pintype "unspecified"))
      (node (ref "U20") (pin "1") (pinfunction "A_1") (pintype "unspecified"))
      (node (ref "U20") (pin "3") (pinfunction "A_3") (pintype "unspecified"))
      (node (ref "U24") (pin "1") (pinfunction "A_1") (pintype "unspecified"))
      (node (ref "U24") (pin "3") (pinfunction "A_3") (pintype "unspecified"))
      (node (ref "U28") (pin "1") (pinfunction "A_1") (pintype "unspecified"))
      (node (ref "U28") (pin "3") (pinfunction "A_3") (pintype "unspecified"))
      (node (ref "U32") (pin "1") (pinfunction "A_1") (pintype "unspecified"))
      (node (ref "U32") (pin "3") (pinfunction "A_3") (pintype "unspecified"))
      (node (ref "U34") (pin "1") (pinfunction "OUT_1") (pintype "output"))
      (node (ref "U34") (pin "4") (pinfunction "IN-_4") (pintype "unspecified"))
      (node (ref "U7") (pin "1") (pinfunction "A_1") (pintype "unspecified"))
      (node (ref "U7") (pin "3") (pinfunction "A_3") (pintype "unspecified"))
    )
    (net (code "8") (name "AI0") (class "Default")
      (node (ref "C41") (pin "2") (pinfunction "2_2") (pintype "unspecified"))
      (node (ref "R65") (pin "1") (pinfunction "1_1") (pintype "unspecified"))
      (node (ref "U35") (pin "6") (pinfunction "AIN0_6") (pintype "unspecified"))
    )
    (net (code "9") (name "AI1") (class "Default")
      (node (ref "C42") (pin "2") (pinfunction "2_2") (pintype "unspecified"))
      (node (ref "R66") (pin "1") (pinfunction "1_1") (pintype "unspecified"))
      (node (ref "U35") (pin "7") (pinfunction "AIN1_7") (pintype "unspecified"))
    )
    (net (code "10") (name "AI2") (class "Default")
      (node (ref "C43") (pin "2") (pinfunction "2_2") (pintype "unspecified"))
      (node (ref "R67") (pin "1") (pinfunction "1_1") (pintype "unspecified"))
      (node (ref "U35") (pin "8") (pinfunction "AIN2_8") (pintype "unspecified"))
    )
    (net (code "11") (name "AI3") (class "Default")
      (node (ref "C44") (pin "2") (pinfunction "2_2") (pintype "unspecified"))
      (node (ref "R68") (pin "1") (pinfunction "1_1") (pintype "unspecified"))
      (node (ref "U35") (pin "9") (pinfunction "AIN3_9") (pintype "unspecified"))
    )
    (net (code "12") (name "AI4") (class "Default")
      (node (ref "C47") (pin "2") (pinfunction "2_2") (pintype "unspecified"))
      (node (ref "R69") (pin "1") (pinfunction "1_1") (pintype "unspecified"))
      (node (ref "U35") (pin "10") (pinfunction "AIN4_10") (pintype "unspecified"))
    )
    (net (code "13") (name "AI5") (class "Default")
      (node (ref "C48") (pin "2") (pinfunction "2_2") (pintype "unspecified"))
      (node (ref "R70") (pin "1") (pinfunction "1_1") (pintype "unspecified"))
      (node (ref "U35") (pin "11") (pinfunction "AIN5_11") (pintype "unspecified"))
    )
    (net (code "14") (name "AI6") (class "Default")
      (node (ref "C49") (pin "2") (pinfunction "2_2") (pintype "unspecified"))
      (node (ref "R71") (pin "1") (pinfunction "1_1") (pintype "unspecified"))
      (node (ref "U35") (pin "12") (pinfunction "AIN6_12") (pintype "unspecified"))
    )
    (net (code "15") (name "AI7") (class "Default")
      (node (ref "C50") (pin "2") (pinfunction "2_2") (pintype "unspecified"))
      (node (ref "R72") (pin "1") (pinfunction "1_1") (pintype "unspecified"))
      (node (ref "U35") (pin "13") (pinfunction "AIN7_13") (pintype "unspecified"))
    )
    (net (code "16") (name "AIN0") (class "Default")
      (node (ref "R65") (pin "2") (pinfunction "2_2") (pintype "unspecified"))
      (node (ref "U2") (pin "6") (pinfunction "VOUT_6") (pintype "unspecified"))
    )
    (net (code "17") (name "AIN1") (class "Default")
      (node (ref "R66") (pin "2") (pinfunction "2_2") (pintype "unspecified"))
      (node (ref "U3") (pin "6") (pinfunction "VOUT_6") (pintype "unspecified"))
    )
    (net (code "18") (name "AIN2") (class "Default")
      (node (ref "R67") (pin "2") (pinfunction "2_2") (pintype "unspecified"))
      (node (ref "U9") (pin "6") (pinfunction "VOUT_6") (pintype "unspecified"))
    )
    (net (code "19") (name "AIN3") (class "Default")
      (node (ref "R68") (pin "2") (pinfunction "2_2") (pintype "unspecified"))
      (node (ref "U25") (pin "6") (pinfunction "VOUT_6") (pintype "unspecified"))
    )
    (net (code "20") (name "AIN4") (class "Default")
      (node (ref "R69") (pin "2") (pinfunction "2_2") (pintype "unspecified"))
      (node (ref "U29") (pin "6") (pinfunction "VOUT_6") (pintype "unspecified"))
    )
    (net (code "21") (name "AIN5") (class "Default")
      (node (ref "R70") (pin "2") (pinfunction "2_2") (pintype "unspecified"))
      (node (ref "U21") (pin "6") (pinfunction "VOUT_6") (pintype "unspecified"))
    )
    (net (code "22") (name "AIN6") (class "Default")
      (node (ref "R71") (pin "2") (pinfunction "2_2") (pintype "unspecified"))
      (node (ref "U17") (pin "6") (pinfunction "VOUT_6") (pintype "unspecified"))
    )
    (net (code "23") (name "AIN7") (class "Default")
      (node (ref "R72") (pin "2") (pinfunction "2_2") (pintype "unspecified"))
      (node (ref "U13") (pin "6") (pinfunction "VOUT_6") (pintype "unspecified"))
    )
    (net (code "24") (name "ANT") (class "Default")
      (node (ref "G$1") (pin "SIG") (pinfunction "SIG_SIG") (pintype "bidirectional"))
      (node (ref "U45") (pin "6") (pinfunction "ANT_6") (pintype "unspecified"))
    )
    (net (code "25") (name "B") (class "Default")
      (node (ref "CN3") (pin "1") (pinfunction "1_1") (pintype "unspecified"))
      (node (ref "D6") (pin "1") (pinfunction "1_1") (pintype "unspecified"))
      (node (ref "U47") (pin "7") (pinfunction "B_7") (pintype "unspecified"))
    )
    (net (code "26") (name "BATMON") (class "Default")
      (node (ref "C71") (pin "2") (pinfunction "2_2") (pintype "unspecified"))
      (node (ref "R82") (pin "2") (pinfunction "2_2") (pintype "input"))
      (node (ref "R83") (pin "1") (pinfunction "1_1") (pintype "input"))
      (node (ref "U49") (pin "4") (pinfunction "IO4_4") (pintype "unspecified"))
    )
    (net (code "27") (name "BUZZER") (class "Default")
      (node (ref "U44") (pin "3") (pinfunction "I3_3") (pintype "unspecified"))
      (node (ref "U49") (pin "33") (pinfunction "IO40_33") (pintype "unspecified"))
    )
    (net (code "28") (name "CFG") (class "Default")
      (node (ref "R80") (pin "2") (pinfunction "2_2") (pintype "input"))
      (node (ref "SW1") (pin "1") (pinfunction "1_1") (pintype "input"))
      (node (ref "U49") (pin "9") (pinfunction "IO16_9") (pintype "unspecified"))
    )
    (net (code "29") (name "CLR") (class "Default")
      (node (ref "R107") (pin "1") (pinfunction "1_1") (pintype "input"))
      (node (ref "U49") (pin "31") (pinfunction "IO38_31") (pintype "unspecified"))
      (node (ref "U51") (pin "6") (pinfunction "#CLR_6") (pintype "unspecified"))
    )
    (net (code "30") (name "D+") (class "Default")
      (node (ref "D5") (pin "2") (pinfunction "2_2") (pintype "unspecified"))
      (node (ref "U48") (pin "5") (pinfunction "D+_5") (pintype "unspecified"))
      (node (ref "USB1") (pin "3") (pinfunction "D+_3") (pintype "unspecified"))
    )
    (net (code "31") (name "D-") (class "Default")
      (node (ref "D4") (pin "2") (pinfunction "2_2") (pintype "unspecified"))
      (node (ref "U48") (pin "6") (pinfunction "D-_6") (pintype "unspecified"))
      (node (ref "USB1") (pin "2") (pinfunction "D-_2") (pintype "unspecified"))
    )
    (net (code "32") (name "DCFAN") (class "Default")
      (node (ref "U44") (pin "1") (pinfunction "I1_1") (pintype "unspecified"))
      (node (ref "U49") (pin "35") (pinfunction "IO42_35") (pintype "unspecified"))
    )
    (net (code "33") (name "DIO1") (class "Default")
      (node (ref "U45") (pin "20") (pinfunction "DIO1_20") (pintype "unspecified"))
      (node (ref "U49") (pin "39") (pinfunction "IO1_39") (pintype "unspecified"))
    )
    (net (code "34") (name "DIR") (class "Default")
      (node (ref "U47") (pin "2") (pinfunction "RE#_2") (pintype "unspecified"))
      (node (ref "U47") (pin "3") (pinfunction "DE_3") (pintype "unspecified"))
      (node (ref "U49") (pin "13") (pinfunction "IO19_13") (pintype "unspecified"))
    )
    (net (code "35") (name "DONE") (class "Default")
      (node (ref "U46") (pin "4") (pinfunction "DONE_4") (pintype "unspecified"))
      (node (ref "U49") (pin "22") (pinfunction "IO14_22") (pintype "unspecified"))
    )
    (net (code "36") (name "DRDY") (class "Default")
      (node (ref "U35") (pin "21") (pinfunction "DRDY_21") (pintype "output"))
      (node (ref "U49") (pin "18") (pinfunction "IO10_18") (pintype "unspecified"))
    )
    (net (code "37") (name "DTR") (class "Default")
      (node (ref "Q1") (pin "2") (pinfunction "B1_2") (pintype "unspecified"))
      (node (ref "Q1") (pin "4") (pinfunction "E2_4") (pintype "unspecified"))
      (node (ref "U48") (pin "13") (pinfunction "DTR#_13") (pintype "unspecified"))
    )
    (net (code "38") (name "ENA") (class "Default")
      (node (ref "U41") (pin "2") (pinfunction "EN_2") (pintype "unspecified"))
      (node (ref "U51") (pin "5") (pinfunction "Q_5") (pintype "unspecified"))
    )
    (net (code "39") (name "GND") (class "Default")
      (node (ref "C100") (pin "1") (pinfunction "1_1") (pintype "unspecified"))
      (node (ref "C101") (pin "1") (pinfunction "1_1") (pintype "unspecified"))
      (node (ref "C11") (pin "1") (pinfunction "1_1") (pintype "unspecified"))
      (node (ref "C12") (pin "1") (pinfunction "1_1") (pintype "unspecified"))
      (node (ref "C13") (pin "1") (pinfunction "1_1") (pintype "unspecified"))
      (node (ref "C14") (pin "1") (pinfunction "1_1") (pintype "unspecified"))
      (node (ref "C15") (pin "1") (pinfunction "1_1") (pintype "unspecified"))
      (node (ref "C16") (pin "2") (pinfunction "2_2") (pintype "unspecified"))
      (node (ref "C18") (pin "1") (pinfunction "1_1") (pintype "unspecified"))
      (node (ref "C19") (pin "1") (pinfunction "1_1") (pintype "unspecified"))
      (node (ref "C2") (pin "1") (pinfunction "1_1") (pintype "unspecified"))
      (node (ref "C20") (pin "1") (pinfunction "1_1") (pintype "unspecified"))
      (node (ref "C21") (pin "2") (pinfunction "2_2") (pintype "unspecified"))
      (node (ref "C23") (pin "1") (pinfunction "1_1") (pintype "unspecified"))
      (node (ref "C24") (pin "1") (pinfunction "1_1") (pintype "unspecified"))
      (node (ref "C25") (pin "1") (pinfunction "1_1") (pintype "unspecified"))
      (node (ref "C26") (pin "2") (pinfunction "2_2") (pintype "unspecified"))
      (node (ref "C28") (pin "1") (pinfunction "1_1") (pintype "unspecified"))
      (node (ref "C29") (pin "1") (pinfunction "1_1") (pintype "unspecified"))
      (node (ref "C3") (pin "2") (pinfunction "2_2") (pintype "unspecified"))
      (node (ref "C30") (pin "1") (pinfunction "1_1") (pintype "unspecified"))
      (node (ref "C31") (pin "2") (pinfunction "2_2") (pintype "unspecified"))
      (node (ref "C33") (pin "1") (pinfunction "1_1") (pintype "unspecified"))
      (node (ref "C34") (pin "1") (pinfunction "1_1") (pintype "unspecified"))
      (node (ref "C35") (pin "1") (pinfunction "1_1") (pintype "unspecified"))
      (node (ref "C36") (pin "2") (pinfunction "2_2") (pintype "unspecified"))
      (node (ref "C38") (pin "1") (pinfunction "1_1") (pintype "unspecified"))
      (node (ref "C39") (pin "1") (pinfunction "1_1") (pintype "unspecified"))
      (node (ref "C4") (pin "2") (pinfunction "2_2") (pintype "unspecified"))
      (node (ref "C40") (pin "1") (pinfunction "1_1") (pintype "unspecified"))
      (node (ref "C41") (pin "1") (pinfunction "1_1") (pintype "unspecified"))
      (node (ref "C42") (pin "1") (pinfunction "1_1") (pintype "unspecified"))
      (node (ref "C43") (pin "1") (pinfunction "1_1") (pintype "unspecified"))
      (node (ref "C44") (pin "1") (pinfunction "1_1") (pintype "unspecified"))
      (node (ref "C45") (pin "2") (pinfunction "2_2") (pintype "input"))
      (node (ref "C46") (pin "1") (pinfunction "1_1") (pintype "unspecified"))
      (node (ref "C47") (pin "1") (pinfunction "1_1") (pintype "unspecified"))
      (node (ref "C48") (pin "1") (pinfunction "1_1") (pintype "unspecified"))
      (node (ref "C49") (pin "1") (pinfunction "1_1") (pintype "unspecified"))
      (node (ref "C50") (pin "1") (pinfunction "1_1") (pintype "unspecified"))
      (node (ref "C51") (pin "1") (pinfunction "1_1") (pintype "unspecified"))
      (node (ref "C52") (pin "1") (pinfunction "1_1") (pintype "unspecified"))
      (node (ref "C53") (pin "2") (pinfunction "2_2") (pintype "input"))
      (node (ref "C54") (pin "1") (pinfunction "1_1") (pintype "unspecified"))
      (node (ref "C55") (pin "1") (pinfunction "1_1") (pintype "unspecified"))
      (node (ref "C56") (pin "2") (pinfunction "2_2") (pintype "input"))
      (node (ref "C57") (pin "1") (pinfunction "1_1") (pintype "input"))
      (node (ref "C58") (pin "1") (pinfunction "1_1") (pintype "unspecified"))
      (node (ref "C59") (pin "1") (pinfunction "1_1") (pintype "unspecified"))
      (node (ref "C6") (pin "1") (pinfunction "1_1") (pintype "unspecified"))
      (node (ref "C60") (pin "1") (pinfunction "1_1") (pintype "unspecified"))
      (node (ref "C61") (pin "1") (pinfunction "1_1") (pintype "unspecified"))
      (node (ref "C62") (pin "1") (pinfunction "1_1") (pintype "unspecified"))
      (node (ref "C63") (pin "2") (pinfunction "2_2") (pintype "input"))
      (node (ref "C64") (pin "1") (pinfunction "1_1") (pintype "unspecified"))
      (node (ref "C65") (pin "1") (pinfunction "1_1") (pintype "unspecified"))
      (node (ref "C66") (pin "1") (pinfunction "1_1") (pintype "unspecified"))
      (node (ref "C67") (pin "1") (pinfunction "1_1") (pintype "unspecified"))
      (node (ref "C68") (pin "1") (pinfunction "1_1") (pintype "unspecified"))
      (node (ref "C7") (pin "1") (pinfunction "1_1") (pintype "unspecified"))
      (node (ref "C71") (pin "1") (pinfunction "1_1") (pintype "unspecified"))
      (node (ref "C72") (pin "1") (pinfunction "1_1") (pintype "unspecified"))
      (node (ref "C73") (pin "1") (pinfunction "1_1") (pintype "unspecified"))
      (node (ref "C74") (pin "1") (pinfunction "1_1") (pintype "unspecified"))
      (node (ref "C75") (pin "1") (pinfunction "1_1") (pintype "unspecified"))
      (node (ref "C77") (pin "1") (pinfunction "1_1") (pintype "input"))
      (node (ref "C78") (pin "1") (pinfunction "1_1") (pintype "unspecified"))
      (node (ref "C79") (pin "1") (pinfunction "1_1") (pintype "unspecified"))
      (node (ref "C8") (pin "1") (pinfunction "1_1") (pintype "unspecified"))
      (node (ref "C80") (pin "1") (pinfunction "1_1") (pintype "unspecified"))
      (node (ref "C81") (pin "1") (pinfunction "1_1") (pintype "unspecified"))
      (node (ref "C82") (pin "2") (pinfunction "2_2") (pintype "input"))
      (node (ref "C83") (pin "2") (pinfunction "2_2") (pintype "input"))
      (node (ref "C84") (pin "1") (pinfunction "1_1") (pintype "input"))
      (node (ref "C85") (pin "1") (pinfunction "1_1") (pintype "unspecified"))
      (node (ref "C86") (pin "1") (pinfunction "1_1") (pintype "unspecified"))
      (node (ref "C87") (pin "1") (pinfunction "1_1") (pintype "unspecified"))
      (node (ref "C88") (pin "1") (pinfunction "1_1") (pintype "unspecified"))
      (node (ref "C89") (pin "1") (pinfunction "1_1") (pintype "unspecified"))
      (node (ref "C9") (pin "2") (pinfunction "2_2") (pintype "unspecified"))
      (node (ref "C90") (pin "1") (pinfunction "1_1") (pintype "unspecified"))
      (node (ref "C91") (pin "1") (pinfunction "1_1") (pintype "unspecified"))
      (node (ref "C92") (pin "1") (pinfunction "1_1") (pintype "unspecified"))
      (node (ref "C93") (pin "1") (pinfunction "1_1") (pintype "input"))
      (node (ref "C94") (pin "1") (pinfunction "1_1") (pintype "unspecified"))
      (node (ref "C95") (pin "1") (pinfunction "1_1") (pintype "unspecified"))
      (node (ref "C96") (pin "1") (pinfunction "1_1") (pintype "unspecified"))
      (node (ref "C97") (pin "1") (pinfunction "1_1") (pintype "unspecified"))
      (node (ref "C98") (pin "1") (pinfunction "1_1") (pintype "unspecified"))
      (node (ref "C99") (pin "1") (pinfunction "1_1") (pintype "unspecified"))
      (node (ref "CN2") (pin "2") (pinfunction "2_2") (pintype "unspecified"))
      (node (ref "D1") (pin "2") (pinfunction "A_2") (pintype "unspecified"))
      (node (ref "D4") (pin "1") (pinfunction "1_1") (pintype "unspecified"))
      (node (ref "D5") (pin "1") (pinfunction "1_1") (pintype "unspecified"))
      (node (ref "D6") (pin "3") (pinfunction "3_3") (pintype "unspecified"))
      (node (ref "G$1") (pin "GND1") (pinfunction "GND_GND1") (pintype "bidirectional"))
      (node (ref "G$1") (pin "GND2") (pinfunction "GND_GND2") (pintype "bidirectional"))
      (node (ref "J2") (pin "4") (pinfunction "4_4") (pintype "unspecified"))
      (node (ref "R105") (pin "1") (pinfunction "1_1") (pintype "input"))
      (node (ref "R79") (pin "1") (pinfunction "1_1") (pintype "input"))
      (node (ref "R81") (pin "1") (pinfunction "1_1") (pintype "input"))
      (node (ref "R82") (pin "1") (pinfunction "1_1") (pintype "input"))
      (node (ref "R86") (pin "1") (pinfunction "1_1") (pintype "input"))
      (node (ref "R89") (pin "2") (pinfunction "2_2") (pintype "input"))
      (node (ref "R92") (pin "1") (pinfunction "1_1") (pintype "input"))
      (node (ref "R99") (pin "2") (pinfunction "2_2") (pintype "input"))
      (node (ref "SW1") (pin "2") (pinfunction "2_2") (pintype "input"))
      (node (ref "U1") (pin "6") (pinfunction "H_6") (pintype "unspecified"))
      (node (ref "U10") (pin "2") (pinfunction "V-_2") (pintype "passive"))
      (node (ref "U11") (pin "2") (pinfunction "VSS_2") (pintype "unspecified"))
      (node (ref "U11") (pin "6") (pinfunction "A0_6") (pintype "unspecified"))
      (node (ref "U12") (pin "6") (pinfunction "H_6") (pintype "unspecified"))
      (node (ref "U13") (pin "4") (pinfunction "V-_4") (pintype "unspecified"))
      (node (ref "U14") (pin "2") (pinfunction "V-_2") (pintype "passive"))
      (node (ref "U15") (pin "2") (pinfunction "VSS_2") (pintype "unspecified"))
      (node (ref "U15") (pin "6") (pinfunction "A0_6") (pintype "unspecified"))
      (node (ref "U16") (pin "6") (pinfunction "H_6") (pintype "unspecified"))
      (node (ref "U17") (pin "4") (pinfunction "V-_4") (pintype "unspecified"))
      (node (ref "U18") (pin "2") (pinfunction "V-_2") (pintype "passive"))
      (node (ref "U19") (pin "2") (pinfunction "VSS_2") (pintype "unspecified"))
      (node (ref "U19") (pin "6") (pinfunction "A0_6") (pintype "unspecified"))
      (node (ref "U2") (pin "4") (pinfunction "V-_4") (pintype "unspecified"))
      (node (ref "U20") (pin "6") (pinfunction "H_6") (pintype "unspecified"))
      (node (ref "U21") (pin "4") (pinfunction "V-_4") (pintype "unspecified"))
      (node (ref "U22") (pin "2") (pinfunction "V-_2") (pintype "passive"))
      (node (ref "U23") (pin "2") (pinfunction "VSS_2") (pintype "unspecified"))
      (node (ref "U23") (pin "6") (pinfunction "A0_6") (pintype "unspecified"))
      (node (ref "U24") (pin "6") (pinfunction "H_6") (pintype "unspecified"))
      (node (ref "U25") (pin "4") (pinfunction "V-_4") (pintype "unspecified"))
      (node (ref "U26") (pin "2") (pinfunction "V-_2") (pintype "passive"))
      (node (ref "U27") (pin "2") (pinfunction "VSS_2") (pintype "unspecified"))
      (node (ref "U27") (pin "6") (pinfunction "A0_6") (pintype "unspecified"))
      (node (ref "U28") (pin "6") (pinfunction "H_6") (pintype "unspecified"))
      (node (ref "U29") (pin "4") (pinfunction "V-_4") (pintype "unspecified"))
      (node (ref "U3") (pin "4") (pinfunction "V-_4") (pintype "unspecified"))
      (node (ref "U30") (pin "2") (pinfunction "V-_2") (pintype "passive"))
      (node (ref "U31") (pin "2") (pinfunction "VSS_2") (pintype "unspecified"))
      (node (ref "U31") (pin "6") (pinfunction "A0_6") (pintype "unspecified"))
      (node (ref "U32") (pin "6") (pinfunction "H_6") (pintype "unspecified"))
      (node (ref "U33") (pin "12") (pinfunction "GND_12") (pintype "unspecified"))
      (node (ref "U33") (pin "2") (pinfunction "A1_2") (pintype "unspecified"))
      (node (ref "U33") (pin "21") (pinfunction "A2_21") (pintype "unspecified"))
      (node (ref "U34") (pin "2") (pinfunction "V-_2") (pintype "passive"))
      (node (ref "U35") (pin "17") (pinfunction "DGND_17") (pintype "passive"))
      (node (ref "U35") (pin "2") (pinfunction "AGND_2") (pintype "passive"))
      (node (ref "U35") (pin "3") (pinfunction "VREFN_3") (pintype "unspecified"))
      (node (ref "U35") (pin "5") (pinfunction "AINCOM_5") (pintype "unspecified"))
      (node (ref "U36") (pin "13") (pinfunction "EP_13") (pintype "unspecified"))
      (node (ref "U36") (pin "8") (pinfunction "AGND_8") (pintype "unspecified"))
      (node (ref "U37") (pin "2") (pinfunction "V-_2") (pintype "passive"))
      (node (ref "U38") (pin "2") (pinfunction "GND_2") (pintype "unspecified"))
      (node (ref "U39") (pin "2") (pinfunction "GND_2") (pintype "input"))
      (node (ref "U39") (pin "4") (pinfunction "GND_4") (pintype "input"))
      (node (ref "U4") (pin "2") (pinfunction "V-_2") (pintype "passive"))
      (node (ref "U41") (pin "20") (pinfunction "AGND_20") (pintype "unspecified"))
      (node (ref "U41") (pin "21") (pinfunction "PGND_21") (pintype "unspecified"))
      (node (ref "U42") (pin "2") (pinfunction "GND_2") (pintype "unspecified"))
      (node (ref "U43") (pin "1") (pinfunction "PGND_1") (pintype "passive"))
      (node (ref "U43") (pin "4") (pinfunction "AGND_4") (pintype "passive"))
      (node (ref "U43") (pin "5") (pinfunction "FB_5") (pintype "unspecified"))
      (node (ref "U43") (pin "9") (pinfunction "EP_9") (pintype "passive"))
      (node (ref "U44") (pin "8") (pinfunction "GND_8") (pintype "unspecified"))
      (node (ref "U45") (pin "16") (pinfunction "GND_16") (pintype "unspecified"))
      (node (ref "U45") (pin "2") (pinfunction "GND_2") (pintype "unspecified"))
      (node (ref "U45") (pin "7") (pinfunction "GND_7") (pintype "unspecified"))
      (node (ref "U46") (pin "2") (pinfunction "GND_2") (pintype "unspecified"))
      (node (ref "U47") (pin "5") (pinfunction "GND_5") (pintype "unspecified"))
      (node (ref "U48") (pin "1") (pinfunction "GND_1") (pintype "unspecified"))
      (node (ref "U49") (pin "1") (pinfunction "GND_1") (pintype "passive"))
      (node (ref "U49") (pin "40") (pinfunction "GND_40") (pintype "passive"))
      (node (ref "U49") (pin "41") (pinfunction "GND_41") (pintype "passive"))
      (node (ref "U5") (pin "2") (pinfunction "V-_2") (pintype "passive"))
      (node (ref "U51") (pin "4") (pinfunction "GND_4") (pintype "unspecified"))
      (node (ref "U52") (pin "3") (pinfunction "GND_3") (pintype "unspecified"))
      (node (ref "U6") (pin "2") (pinfunction "VSS_2") (pintype "unspecified"))
      (node (ref "U6") (pin "6") (pinfunction "A0_6") (pintype "unspecified"))
      (node (ref "U7") (pin "6") (pinfunction "H_6") (pintype "unspecified"))
      (node (ref "U8") (pin "2") (pinfunction "VSS_2") (pintype "unspecified"))
      (node (ref "U8") (pin "6") (pinfunction "A0_6") (pintype "unspecified"))
      (node (ref "U9") (pin "4") (pinfunction "V-_4") (pintype "unspecified"))
      (node (ref "USB1") (pin "5") (pinfunction "GND_5") (pintype "unspecified"))
      (node (ref "USB1") (pin "6") (pinfunction "EP_6") (pintype "unspecified"))
      (node (ref "USB1") (pin "7") (pinfunction "EP_7") (pintype "unspecified"))
    )
    (net (code "40") (name "IO0") (class "Default")
      (node (ref "C90") (pin "2") (pinfunction "2_2") (pintype "unspecified"))
      (node (ref "Q1") (pin "3") (pinfunction "C2_3") (pintype "unspecified"))
      (node (ref "R94") (pin "1") (pinfunction "1_1") (pintype "input"))
      (node (ref "U49") (pin "27") (pinfunction "IO0_27") (pintype "unspecified"))
    )
    (net (code "41") (name "LAMP") (class "Default")
      (node (ref "U44") (pin "2") (pinfunction "I2_2") (pintype "unspecified"))
      (node (ref "U49") (pin "34") (pinfunction "IO41_34") (pintype "unspecified"))
    )
    (net (code "42") (name "LED") (class "Default")
      (node (ref "R93") (pin "1") (pinfunction "1_1") (pintype "input"))
      (node (ref "U49") (pin "32") (pinfunction "IO39_32") (pintype "unspecified"))
    )
    (net (code "43") (name "LORA_BUSY") (class "Default")
      (node (ref "U45") (pin "11") (pinfunction "BUSY_11") (pintype "unspecified"))
      (node (ref "U49") (pin "8") (pinfunction "IO15_8") (pintype "unspecified"))
    )
    (net (code "44") (name "LORA_RST") (class "Default")
      (node (ref "U45") (pin "3") (pinfunction "NRST_3") (pintype "unspecified"))
      (node (ref "U49") (pin "38") (pinfunction "IO2_38") (pintype "unspecified"))
    )
    (net (code "45") (name "LORA_SS") (class "Default")
      (node (ref "U45") (pin "14") (pinfunction "NSS_14") (pintype "unspecified"))
      (node (ref "U49") (pin "7") (pinfunction "IO7_7") (pintype "unspecified"))
    )
    (net (code "46") (name "Net-(C69-Pad1)") (class "Default")
      (node (ref "C69") (pin "1") (pinfunction "1_1") (pintype "unspecified"))
      (node (ref "U36") (pin "1") (pinfunction "SW_1") (pintype "unspecified"))
      (node (ref "U36") (pin "2") (pinfunction "SW_2") (pintype "unspecified"))
      (node (ref "U36") (pin "3") (pinfunction "SW_3") (pintype "unspecified"))
      (node (ref "U40") (pin "1") (pinfunction "1_1") (pintype "unspecified"))
    )
    (net (code "47") (name "Net-(C70-Pad1)") (class "Default")
      (node (ref "C70") (pin "1") (pinfunction "1_1") (pintype "input"))
      (node (ref "R87") (pin "1") (pinfunction "1_1") (pintype "input"))
    )
    (net (code "48") (name "Net-(C76-Pad2)") (class "Default")
      (node (ref "C76") (pin "2") (pinfunction "2_2") (pintype "unspecified"))
      (node (ref "L2") (pin "2") (pinfunction "2_2") (pintype "unspecified"))
      (node (ref "R88") (pin "1") (pinfunction "1_1") (pintype "input"))
      (node (ref "U41") (pin "4") (pinfunction "SW_4") (pintype "unspecified"))
      (node (ref "U41") (pin "5") (pinfunction "SW_5") (pintype "unspecified"))
      (node (ref "U41") (pin "6") (pinfunction "SW_6") (pintype "unspecified"))
      (node (ref "U41") (pin "7") (pinfunction "SW_7") (pintype "unspecified"))
    )
    (net (code "49") (name "Net-(C82-Pad1)") (class "Default")
      (node (ref "C82") (pin "1") (pinfunction "1_1") (pintype "input"))
      (node (ref "R91") (pin "2") (pinfunction "2_2") (pintype "input"))
    )
    (net (code "50") (name "Net-(CN2-Pad1)") (class "Default")
      (node (ref "CN2") (pin "1") (pinfunction "1_1") (pintype "unspecified"))
      (node (ref "J1") (pin "1") (pinfunction "1_1") (pintype "input"))
      (node (ref "J1") (pin "3") (pinfunction "3_3") (pintype "input"))
      (node (ref "J1") (pin "5") (pinfunction "5_5") (pintype "input"))
    )
    (net (code "51") (name "Net-(D1-K)") (class "Default")
      (node (ref "D1") (pin "1") (pinfunction "K_1") (pintype "unspecified"))
      (node (ref "D2") (pin "1") (pinfunction "K_1") (pintype "unspecified"))
      (node (ref "F1") (pin "2") (pinfunction "2_2") (pintype "unspecified"))
      (node (ref "Q3") (pin "1") (pinfunction "S_1") (pintype "unspecified"))
      (node (ref "Q3") (pin "2") (pinfunction "S_2") (pintype "unspecified"))
      (node (ref "Q3") (pin "3") (pinfunction "S_3") (pintype "unspecified"))
    )
    (net (code "52") (name "Net-(D2-A)") (class "Default")
      (node (ref "D2") (pin "2") (pinfunction "A_2") (pintype "unspecified"))
      (node (ref "Q3") (pin "4") (pinfunction "G_4") (pintype "unspecified"))
      (node (ref "R81") (pin "2") (pinfunction "2_2") (pintype "input"))
    )
    (net (code "53") (name "Net-(D3-K)") (class "Default")
      (node (ref "C97") (pin "2") (pinfunction "2_2") (pintype "unspecified"))
      (node (ref "D3") (pin "3") (pinfunction "K_3") (pintype "unspecified"))
      (node (ref "R100") (pin "2") (pinfunction "2_2") (pintype "input"))
      (node (ref "U42") (pin "1") (pinfunction "IN_1") (pintype "unspecified"))
    )
    (net (code "54") (name "Net-(D9-A)") (class "Default")
      (node (ref "C78") (pin "2") (pinfunction "2_2") (pintype "unspecified"))
      (node (ref "C79") (pin "2") (pinfunction "2_2") (pintype "unspecified"))
      (node (ref "C80") (pin "2") (pinfunction "2_2") (pintype "unspecified"))
      (node (ref "C81") (pin "2") (pinfunction "2_2") (pintype "unspecified"))
      (node (ref "D9") (pin "1") (pinfunction "A_1") (pintype "unspecified"))
      (node (ref "R90") (pin "1") (pinfunction "1_1") (pintype "input"))
      (node (ref "U41") (pin "14") (pinfunction "VOUT_14") (pintype "unspecified"))
      (node (ref "U41") (pin "15") (pinfunction "VOUT_15") (pintype "unspecified"))
      (node (ref "U41") (pin "16") (pinfunction "VOUT_16") (pintype "unspecified"))
    )
    (net (code "55") (name "Net-(F1-Pad1)") (class "Default")
      (node (ref "F1") (pin "1") (pinfunction "1_1") (pintype "unspecified"))
      (node (ref "J1") (pin "6") (pinfunction "6_6") (pintype "input"))
    )
    (net (code "56") (name "Net-(LED1-C)") (class "Default")
      (node (ref "LED1") (pin "2") (pinfunction "C_2") (pintype "input"))
      (node (ref "R93") (pin "2") (pinfunction "2_2") (pintype "input"))
    )
    (net (code "57") (name "Net-(R1-Pad1)") (class "Default")
      (node (ref "R1") (pin "1") (pinfunction "1_1") (pintype "input"))
      (node (ref "U2") (pin "1") (pinfunction "RG_1") (pintype "unspecified"))
    )
    (net (code "58") (name "Net-(R1-Pad2)") (class "Default")
      (node (ref "R1") (pin "2") (pinfunction "2_2") (pintype "input"))
      (node (ref "U2") (pin "8") (pinfunction "RG_8") (pintype "unspecified"))
    )
    (net (code "59") (name "Net-(R2-Pad1)") (class "Default")
      (node (ref "R2") (pin "1") (pinfunction "1_1") (pintype "input"))
      (node (ref "U3") (pin "1") (pinfunction "RG_1") (pintype "unspecified"))
    )
    (net (code "60") (name "Net-(R2-Pad2)") (class "Default")
      (node (ref "R2") (pin "2") (pinfunction "2_2") (pintype "input"))
      (node (ref "U3") (pin "8") (pinfunction "RG_8") (pintype "unspecified"))
    )
    (net (code "61") (name "Net-(R3-Pad2)") (class "Default")
      (node (ref "R3") (pin "2") (pinfunction "2_2") (pintype "input"))
      (node (ref "R4") (pin "2") (pinfunction "2_2") (pintype "input"))
      (node (ref "R9") (pin "1") (pinfunction "1_1") (pintype "unspecified"))
      (node (ref "U7") (pin "5") (pinfunction "B_5") (pintype "unspecified"))
      (node (ref "U7") (pin "7") (pinfunction "B_7") (pintype "unspecified"))
    )
    (net (code "62") (name "Net-(R10-Pad2)") (class "Default")
      (node (ref "R10") (pin "2") (pinfunction "2_2") (pintype "input"))
      (node (ref "R7") (pin "1") (pinfunction "1_1") (pintype "input"))
      (node (ref "R8") (pin "1") (pinfunction "1_1") (pintype "unspecified"))
    )
    (net (code "63") (name "Net-(R11-Pad1)") (class "Default")
      (node (ref "R11") (pin "1") (pinfunction "1_1") (pintype "unspecified"))
      (node (ref "R22") (pin "2") (pinfunction "2_2") (pintype "input"))
      (node (ref "R23") (pin "2") (pinfunction "2_2") (pintype "input"))
      (node (ref "U1") (pin "5") (pinfunction "B_5") (pintype "unspecified"))
      (node (ref "U1") (pin "7") (pinfunction "B_7") (pintype "unspecified"))
    )
    (net (code "64") (name "Net-(R13-Pad1)") (class "Default")
      (node (ref "R13") (pin "1") (pinfunction "1_1") (pintype "input"))
      (node (ref "U9") (pin "1") (pinfunction "RG_1") (pintype "unspecified"))
    )
    (net (code "65") (name "Net-(R13-Pad2)") (class "Default")
      (node (ref "R13") (pin "2") (pinfunction "2_2") (pintype "input"))
      (node (ref "U9") (pin "8") (pinfunction "RG_8") (pintype "unspecified"))
    )
    (net (code "66") (name "Net-(R14-Pad1)") (class "Default")
      (node (ref "R14") (pin "1") (pinfunction "1_1") (pintype "unspecified"))
      (node (ref "R5") (pin "1") (pinfunction "1_1") (pintype "input"))
      (node (ref "R6") (pin "2") (pinfunction "2_2") (pintype "input"))
    )
    (net (code "67") (name "Net-(R15-Pad2)") (class "Default")
      (node (ref "R15") (pin "2") (pinfunction "2_2") (pintype "input"))
      (node (ref "R16") (pin "2") (pinfunction "2_2") (pintype "input"))
      (node (ref "R19") (pin "1") (pinfunction "1_1") (pintype "unspecified"))
      (node (ref "U12") (pin "5") (pinfunction "B_5") (pintype "unspecified"))
      (node (ref "U12") (pin "7") (pinfunction "B_7") (pintype "unspecified"))
    )
    (net (code "68") (name "Net-(R17-Pad1)") (class "Default")
      (node (ref "R17") (pin "1") (pinfunction "1_1") (pintype "input"))
      (node (ref "R18") (pin "1") (pinfunction "1_1") (pintype "unspecified"))
      (node (ref "R20") (pin "2") (pinfunction "2_2") (pintype "input"))
    )
    (net (code "69") (name "Net-(R25-Pad1)") (class "Default")
      (node (ref "R25") (pin "1") (pinfunction "1_1") (pintype "input"))
      (node (ref "U13") (pin "1") (pinfunction "RG_1") (pintype "unspecified"))
    )
    (net (code "70") (name "Net-(R25-Pad2)") (class "Default")
      (node (ref "R25") (pin "2") (pinfunction "2_2") (pintype "input"))
      (node (ref "U13") (pin "8") (pinfunction "RG_8") (pintype "unspecified"))
    )
    (net (code "71") (name "Net-(R26-Pad2)") (class "Default")
      (node (ref "R26") (pin "2") (pinfunction "2_2") (pintype "input"))
      (node (ref "R27") (pin "2") (pinfunction "2_2") (pintype "input"))
      (node (ref "R30") (pin "1") (pinfunction "1_1") (pintype "unspecified"))
      (node (ref "U16") (pin "5") (pinfunction "B_5") (pintype "unspecified"))
      (node (ref "U16") (pin "7") (pinfunction "B_7") (pintype "unspecified"))
    )
    (net (code "72") (name "Net-(R28-Pad1)") (class "Default")
      (node (ref "R28") (pin "1") (pinfunction "1_1") (pintype "input"))
      (node (ref "R29") (pin "1") (pinfunction "1_1") (pintype "unspecified"))
      (node (ref "R31") (pin "2") (pinfunction "2_2") (pintype "input"))
    )
    (net (code "73") (name "Net-(R33-Pad1)") (class "Default")
      (node (ref "R33") (pin "1") (pinfunction "1_1") (pintype "input"))
      (node (ref "U17") (pin "1") (pinfunction "RG_1") (pintype "unspecified"))
    )
    (net (code "74") (name "Net-(R33-Pad2)") (class "Default")
      (node (ref "R33") (pin "2") (pinfunction "2_2") (pintype "input"))
      (node (ref "U17") (pin "8") (pinfunction "RG_8") (pintype "unspecified"))
    )
    (net (code "75") (name "Net-(R34-Pad2)") (class "Default")
      (node (ref "R34") (pin "2") (pinfunction "2_2") (pintype "input"))
      (node (ref "R35") (pin "2") (pinfunction "2_2") (pintype "input"))
      (node (ref "R38") (pin "1") (pinfunction "1_1") (pintype "unspecified"))
      (node (ref "U20") (pin "5") (pinfunction "B_5") (pintype "unspecified"))
      (node (ref "U20") (pin "7") (pinfunction "B_7") (pintype "unspecified"))
    )
    (net (code "76") (name "Net-(R36-Pad1)") (class "Default")
      (node (ref "R36") (pin "1") (pinfunction "1_1") (pintype "input"))
      (node (ref "R37") (pin "1") (pinfunction "1_1") (pintype "unspecified"))
      (node (ref "R39") (pin "2") (pinfunction "2_2") (pintype "input"))
    )
    (net (code "77") (name "Net-(R41-Pad1)") (class "Default")
      (node (ref "R41") (pin "1") (pinfunction "1_1") (pintype "input"))
      (node (ref "U21") (pin "1") (pinfunction "RG_1") (pintype "unspecified"))
    )
    (net (code "78") (name "Net-(R41-Pad2)") (class "Default")
      (node (ref "R41") (pin "2") (pinfunction "2_2") (pintype "input"))
      (node (ref "U21") (pin "8") (pinfunction "RG_8") (pintype "unspecified"))
    )
    (net (code "79") (name "Net-(R42-Pad2)") (class "Default")
      (node (ref "R42") (pin "2") (pinfunction "2_2") (pintype "input"))
      (node (ref "R43") (pin "2") (pinfunction "2_2") (pintype "input"))
      (node (ref "R46") (pin "1") (pinfunction "1_1") (pintype "unspecified"))
      (node (ref "U24") (pin "5") (pinfunction "B_5") (pintype "unspecified"))
      (node (ref "U24") (pin "7") (pinfunction "B_7") (pintype "unspecified"))
    )
    (net (code "80") (name "Net-(R44-Pad1)") (class "Default")
      (node (ref "R44") (pin "1") (pinfunction "1_1") (pintype "input"))
      (node (ref "R45") (pin "1") (pinfunction "1_1") (pintype "unspecified"))
      (node (ref "R47") (pin "2") (pinfunction "2_2") (pintype "input"))
    )
    (net (code "81") (name "Net-(R49-Pad1)") (class "Default")
      (node (ref "R49") (pin "1") (pinfunction "1_1") (pintype "input"))
      (node (ref "U25") (pin "1") (pinfunction "RG_1") (pintype "unspecified"))
    )
    (net (code "82") (name "Net-(R49-Pad2)") (class "Default")
      (node (ref "R49") (pin "2") (pinfunction "2_2") (pintype "input"))
      (node (ref "U25") (pin "8") (pinfunction "RG_8") (pintype "unspecified"))
    )
    (net (code "83") (name "Net-(R50-Pad2)") (class "Default")
      (node (ref "R50") (pin "2") (pinfunction "2_2") (pintype "input"))
      (node (ref "R51") (pin "2") (pinfunction "2_2") (pintype "input"))
      (node (ref "R54") (pin "1") (pinfunction "1_1") (pintype "unspecified"))
      (node (ref "U28") (pin "5") (pinfunction "B_5") (pintype "unspecified"))
      (node (ref "U28") (pin "7") (pinfunction "B_7") (pintype "unspecified"))
    )
    (net (code "84") (name "Net-(R52-Pad1)") (class "Default")
      (node (ref "R52") (pin "1") (pinfunction "1_1") (pintype "input"))
      (node (ref "R53") (pin "1") (pinfunction "1_1") (pintype "unspecified"))
      (node (ref "R55") (pin "2") (pinfunction "2_2") (pintype "input"))
    )
    (net (code "85") (name "Net-(R57-Pad1)") (class "Default")
      (node (ref "R57") (pin "1") (pinfunction "1_1") (pintype "input"))
      (node (ref "U29") (pin "1") (pinfunction "RG_1") (pintype "unspecified"))
    )
    (net (code "86") (name "Net-(R57-Pad2)") (class "Default")
      (node (ref "R57") (pin "2") (pinfunction "2_2") (pintype "input"))
      (node (ref "U29") (pin "8") (pinfunction "RG_8") (pintype "unspecified"))
    )
    (net (code "87") (name "Net-(R58-Pad2)") (class "Default")
      (node (ref "R58") (pin "2") (pinfunction "2_2") (pintype "input"))
      (node (ref "R59") (pin "2") (pinfunction "2_2") (pintype "input"))
      (node (ref "R62") (pin "1") (pinfunction "1_1") (pintype "unspecified"))
      (node (ref "U32") (pin "5") (pinfunction "B_5") (pintype "unspecified"))
      (node (ref "U32") (pin "7") (pinfunction "B_7") (pintype "unspecified"))
    )
    (net (code "88") (name "Net-(R60-Pad1)") (class "Default")
      (node (ref "R60") (pin "1") (pinfunction "1_1") (pintype "input"))
      (node (ref "R61") (pin "1") (pinfunction "1_1") (pintype "unspecified"))
      (node (ref "R63") (pin "2") (pinfunction "2_2") (pintype "input"))
    )
    (net (code "89") (name "Net-(U2-REF)") (class "Default")
      (node (ref "C3") (pin "1") (pinfunction "1_1") (pintype "unspecified"))
      (node (ref "R21") (pin "2") (pinfunction "2_2") (pintype "unspecified"))
      (node (ref "U2") (pin "5") (pinfunction "REF_5") (pintype "unspecified"))
    )
    (net (code "90") (name "Net-(U2-VIN+)") (class "Default")
      (node (ref "C1") (pin "1") (pinfunction "1_1") (pintype "unspecified"))
      (node (ref "R14") (pin "2") (pinfunction "2_2") (pintype "unspecified"))
      (node (ref "U2") (pin "3") (pinfunction "VIN+_3") (pintype "unspecified"))
    )
    (net (code "91") (name "Net-(U2-VIN-)") (class "Default")
      (node (ref "C1") (pin "2") (pinfunction "2_2") (pintype "unspecified"))
      (node (ref "R11") (pin "2") (pinfunction "2_2") (pintype "unspecified"))
      (node (ref "U2") (pin "2") (pinfunction "VIN-_2") (pintype "unspecified"))
    )
    (net (code "92") (name "Net-(U3-REF)") (class "Default")
      (node (ref "C4") (pin "1") (pinfunction "1_1") (pintype "unspecified"))
      (node (ref "R12") (pin "2") (pinfunction "2_2") (pintype "unspecified"))
      (node (ref "U3") (pin "5") (pinfunction "REF_5") (pintype "unspecified"))
    )
    (net (code "93") (name "Net-(U3-VIN+)") (class "Default")
      (node (ref "C5") (pin "1") (pinfunction "1_1") (pintype "unspecified"))
      (node (ref "R8") (pin "2") (pinfunction "2_2") (pintype "unspecified"))
      (node (ref "U3") (pin "3") (pinfunction "VIN+_3") (pintype "unspecified"))
    )
    (net (code "94") (name "Net-(U3-VIN-)") (class "Default")
      (node (ref "C5") (pin "2") (pinfunction "2_2") (pintype "unspecified"))
      (node (ref "R9") (pin "2") (pinfunction "2_2") (pintype "unspecified"))
      (node (ref "U3") (pin "2") (pinfunction "VIN-_2") (pintype "unspecified"))
    )
    (net (code "95") (name "Net-(U4-+IN)") (class "Default")
      (node (ref "U4") (pin "1") (pinfunction "+IN_1") (pintype "unspecified"))
      (node (ref "U6") (pin "1") (pinfunction "VOUT_1") (pintype "unspecified"))
    )
    (net (code "96") (name "Net-(U4--IN)") (class "Default")
      (node (ref "R12") (pin "1") (pinfunction "1_1") (pintype "unspecified"))
      (node (ref "U4") (pin "3") (pinfunction "-IN_3") (pintype "unspecified"))
      (node (ref "U4") (pin "4") (pinfunction "OUT_4") (pintype "output"))
    )
    (net (code "97") (name "Net-(U5-+IN)") (class "Default")
      (node (ref "U5") (pin "1") (pinfunction "+IN_1") (pintype "unspecified"))
      (node (ref "U8") (pin "1") (pinfunction "VOUT_1") (pintype "unspecified"))
    )
    (net (code "98") (name "Net-(U5--IN)") (class "Default")
      (node (ref "R21") (pin "1") (pinfunction "1_1") (pintype "unspecified"))
      (node (ref "U5") (pin "3") (pinfunction "-IN_3") (pintype "unspecified"))
      (node (ref "U5") (pin "4") (pinfunction "OUT_4") (pintype "output"))
    )
    (net (code "99") (name "Net-(U9-REF)") (class "Default")
      (node (ref "C9") (pin "1") (pinfunction "1_1") (pintype "unspecified"))
      (node (ref "R24") (pin "2") (pinfunction "2_2") (pintype "unspecified"))
      (node (ref "U9") (pin "5") (pinfunction "REF_5") (pintype "unspecified"))
    )
    (net (code "100") (name "Net-(U9-VIN+)") (class "Default")
      (node (ref "C10") (pin "1") (pinfunction "1_1") (pintype "unspecified"))
      (node (ref "R18") (pin "2") (pinfunction "2_2") (pintype "unspecified"))
      (node (ref "U9") (pin "3") (pinfunction "VIN+_3") (pintype "unspecified"))
    )
    (net (code "101") (name "Net-(U9-VIN-)") (class "Default")
      (node (ref "C10") (pin "2") (pinfunction "2_2") (pintype "unspecified"))
      (node (ref "R19") (pin "2") (pinfunction "2_2") (pintype "unspecified"))
      (node (ref "U9") (pin "2") (pinfunction "VIN-_2") (pintype "unspecified"))
    )
    (net (code "102") (name "Net-(U10-+IN)") (class "Default")
      (node (ref "U10") (pin "1") (pinfunction "+IN_1") (pintype "unspecified"))
      (node (ref "U11") (pin "1") (pinfunction "VOUT_1") (pintype "unspecified"))
    )
    (net (code "103") (name "Net-(U10--IN)") (class "Default")
      (node (ref "R24") (pin "1") (pinfunction "1_1") (pintype "unspecified"))
      (node (ref "U10") (pin "3") (pinfunction "-IN_3") (pintype "unspecified"))
      (node (ref "U10") (pin "4") (pinfunction "OUT_4") (pintype "output"))
    )
    (net (code "104") (name "Net-(U13-REF)") (class "Default")
      (node (ref "C16") (pin "1") (pinfunction "1_1") (pintype "unspecified"))
      (node (ref "R32") (pin "2") (pinfunction "2_2") (pintype "unspecified"))
      (node (ref "U13") (pin "5") (pinfunction "REF_5") (pintype "unspecified"))
    )
    (net (code "105") (name "Net-(U13-VIN+)") (class "Default")
      (node (ref "C17") (pin "1") (pinfunction "1_1") (pintype "unspecified"))
      (node (ref "R29") (pin "2") (pinfunction "2_2") (pintype "unspecified"))
      (node (ref "U13") (pin "3") (pinfunction "VIN+_3") (pintype "unspecified"))
    )
    (net (code "106") (name "Net-(U13-VIN-)") (class "Default")
      (node (ref "C17") (pin "2") (pinfunction "2_2") (pintype "unspecified"))
      (node (ref "R30") (pin "2") (pinfunction "2_2") (pintype "unspecified"))
      (node (ref "U13") (pin "2") (pinfunction "VIN-_2") (pintype "unspecified"))
    )
    (net (code "107") (name "Net-(U14-+IN)") (class "Default")
      (node (ref "U14") (pin "1") (pinfunction "+IN_1") (pintype "unspecified"))
      (node (ref "U15") (pin "1") (pinfunction "VOUT_1") (pintype "unspecified"))
    )
    (net (code "108") (name "Net-(U14--IN)") (class "Default")
      (node (ref "R32") (pin "1") (pinfunction "1_1") (pintype "unspecified"))
      (node (ref "U14") (pin "3") (pinfunction "-IN_3") (pintype "unspecified"))
      (node (ref "U14") (pin "4") (pinfunction "OUT_4") (pintype "output"))
    )
    (net (code "109") (name "Net-(U17-REF)") (class "Default")
      (node (ref "C21") (pin "1") (pinfunction "1_1") (pintype "unspecified"))
      (node (ref "R40") (pin "2") (pinfunction "2_2") (pintype "unspecified"))
      (node (ref "U17") (pin "5") (pinfunction "REF_5") (pintype "unspecified"))
    )
    (net (code "110") (name "Net-(U17-VIN+)") (class "Default")
      (node (ref "C22") (pin "1") (pinfunction "1_1") (pintype "unspecified"))
      (node (ref "R37") (pin "2") (pinfunction "2_2") (pintype "unspecified"))
      (node (ref "U17") (pin "3") (pinfunction "VIN+_3") (pintype "unspecified"))
    )
    (net (code "111") (name "Net-(U17-VIN-)") (class "Default")
      (node (ref "C22") (pin "2") (pinfunction "2_2") (pintype "unspecified"))
      (node (ref "R38") (pin "2") (pinfunction "2_2") (pintype "unspecified"))
      (node (ref "U17") (pin "2") (pinfunction "VIN-_2") (pintype "unspecified"))
    )
    (net (code "112") (name "Net-(U18-+IN)") (class "Default")
      (node (ref "U18") (pin "1") (pinfunction "+IN_1") (pintype "unspecified"))
      (node (ref "U19") (pin "1") (pinfunction "VOUT_1") (pintype "unspecified"))
    )
    (net (code "113") (name "Net-(U18--IN)") (class "Default")
      (node (ref "R40") (pin "1") (pinfunction "1_1") (pintype "unspecified"))
      (node (ref "U18") (pin "3") (pinfunction "-IN_3") (pintype "unspecified"))
      (node (ref "U18") (pin "4") (pinfunction "OUT_4") (pintype "output"))
    )
    (net (code "114") (name "Net-(U21-REF)") (class "Default")
      (node (ref "C26") (pin "1") (pinfunction "1_1") (pintype "unspecified"))
      (node (ref "R48") (pin "2") (pinfunction "2_2") (pintype "unspecified"))
      (node (ref "U21") (pin "5") (pinfunction "REF_5") (pintype "unspecified"))
    )
    (net (code "115") (name "Net-(U21-VIN+)") (class "Default")
      (node (ref "C27") (pin "1") (pinfunction "1_1") (pintype "unspecified"))
      (node (ref "R45") (pin "2") (pinfunction "2_2") (pintype "unspecified"))
      (node (ref "U21") (pin "3") (pinfunction "VIN+_3") (pintype "unspecified"))
    )
    (net (code "116") (name "Net-(U21-VIN-)") (class "Default")
      (node (ref "C27") (pin "2") (pinfunction "2_2") (pintype "unspecified"))
      (node (ref "R46") (pin "2") (pinfunction "2_2") (pintype "unspecified"))
      (node (ref "U21") (pin "2") (pinfunction "VIN-_2") (pintype "unspecified"))
    )
    (net (code "117") (name "Net-(U22-+IN)") (class "Default")
      (node (ref "U22") (pin "1") (pinfunction "+IN_1") (pintype "unspecified"))
      (node (ref "U23") (pin "1") (pinfunction "VOUT_1") (pintype "unspecified"))
    )
    (net (code "118") (name "Net-(U22--IN)") (class "Default")
      (node (ref "R48") (pin "1") (pinfunction "1_1") (pintype "unspecified"))
      (node (ref "U22") (pin "3") (pinfunction "-IN_3") (pintype "unspecified"))
      (node (ref "U22") (pin "4") (pinfunction "OUT_4") (pintype "output"))
    )
    (net (code "119") (name "Net-(U25-REF)") (class "Default")
      (node (ref "C31") (pin "1") (pinfunction "1_1") (pintype "unspecified"))
      (node (ref "R56") (pin "2") (pinfunction "2_2") (pintype "unspecified"))
      (node (ref "U25") (pin "5") (pinfunction "REF_5") (pintype "unspecified"))
    )
    (net (code "120") (name "Net-(U25-VIN+)") (class "Default")
      (node (ref "C32") (pin "1") (pinfunction "1_1") (pintype "unspecified"))
      (node (ref "R53") (pin "2") (pinfunction "2_2") (pintype "unspecified"))
      (node (ref "U25") (pin "3") (pinfunction "VIN+_3") (pintype "unspecified"))
    )
    (net (code "121") (name "Net-(U25-VIN-)") (class "Default")
      (node (ref "C32") (pin "2") (pinfunction "2_2") (pintype "unspecified"))
      (node (ref "R54") (pin "2") (pinfunction "2_2") (pintype "unspecified"))
      (node (ref "U25") (pin "2") (pinfunction "VIN-_2") (pintype "unspecified"))
    )
    (net (code "122") (name "Net-(U26-+IN)") (class "Default")
      (node (ref "U26") (pin "1") (pinfunction "+IN_1") (pintype "unspecified"))
      (node (ref "U27") (pin "1") (pinfunction "VOUT_1") (pintype "unspecified"))
    )
    (net (code "123") (name "Net-(U26--IN)") (class "Default")
      (node (ref "R56") (pin "1") (pinfunction "1_1") (pintype "unspecified"))
      (node (ref "U26") (pin "3") (pinfunction "-IN_3") (pintype "unspecified"))
      (node (ref "U26") (pin "4") (pinfunction "OUT_4") (pintype "output"))
    )
    (net (code "124") (name "Net-(U29-REF)") (class "Default")
      (node (ref "C36") (pin "1") (pinfunction "1_1") (pintype "unspecified"))
      (node (ref "R64") (pin "2") (pinfunction "2_2") (pintype "unspecified"))
      (node (ref "U29") (pin "5") (pinfunction "REF_5") (pintype "unspecified"))
    )
    (net (code "125") (name "Net-(U29-VIN+)") (class "Default")
      (node (ref "C37") (pin "1") (pinfunction "1_1") (pintype "unspecified"))
      (node (ref "R61") (pin "2") (pinfunction "2_2") (pintype "unspecified"))
      (node (ref "U29") (pin "3") (pinfunction "VIN+_3") (pintype "unspecified"))
    )
    (net (code "126") (name "Net-(U29-VIN-)") (class "Default")
      (node (ref "C37") (pin "2") (pinfunction "2_2") (pintype "unspecified"))
      (node (ref "R62") (pin "2") (pinfunction "2_2") (pintype "unspecified"))
      (node (ref "U29") (pin "2") (pinfunction "VIN-_2") (pintype "unspecified"))
    )
    (net (code "127") (name "Net-(U30-+IN)") (class "Default")
      (node (ref "U30") (pin "1") (pinfunction "+IN_1") (pintype "unspecified"))
      (node (ref "U31") (pin "1") (pinfunction "VOUT_1") (pintype "unspecified"))
    )
    (net (code "128") (name "Net-(U30--IN)") (class "Default")
      (node (ref "R64") (pin "1") (pinfunction "1_1") (pintype "unspecified"))
      (node (ref "U30") (pin "3") (pinfunction "-IN_3") (pintype "unspecified"))
      (node (ref "U30") (pin "4") (pinfunction "OUT_4") (pintype "output"))
    )
    (net (code "129") (name "Net-(U34-IN+)") (class "Default")
      (node (ref "R78") (pin "1") (pinfunction "1_1") (pintype "input"))
      (node (ref "R79") (pin "2") (pinfunction "2_2") (pintype "input"))
      (node (ref "U34") (pin "3") (pinfunction "IN+_3") (pintype "unspecified"))
    )
    (net (code "130") (name "Net-(U35-RESET)") (class "Default")
      (node (ref "R73") (pin "1") (pinfunction "1_1") (pintype "input"))
      (node (ref "U35") (pin "15") (pinfunction "RESET_15") (pintype "unspecified"))
    )
    (net (code "131") (name "Net-(U35-XTAL1CLKIN)") (class "Default")
      (node (ref "C45") (pin "1") (pinfunction "1_1") (pintype "input"))
      (node (ref "U35") (pin "19") (pinfunction "XTAL1CLKIN_19") (pintype "unspecified"))
      (node (ref "U39") (pin "3") (pinfunction "3_3") (pintype "input"))
    )
    (net (code "132") (name "Net-(U35-XTAL2)") (class "Default")
      (node (ref "C57") (pin "2") (pinfunction "2_2") (pintype "input"))
      (node (ref "U35") (pin "18") (pinfunction "XTAL2_18") (pintype "unspecified"))
      (node (ref "U39") (pin "1") (pinfunction "1_1") (pintype "input"))
    )
    (net (code "133") (name "Net-(U36-BOOT)") (class "Default")
      (node (ref "C69") (pin "2") (pinfunction "2_2") (pintype "unspecified"))
      (node (ref "U36") (pin "4") (pinfunction "BOOT_4") (pintype "unspecified"))
    )
    (net (code "134") (name "Net-(U36-EN)") (class "Default")
      (node (ref "C59") (pin "2") (pinfunction "2_2") (pintype "unspecified"))
      (node (ref "C60") (pin "2") (pinfunction "2_2") (pintype "unspecified"))
      (node (ref "C61") (pin "2") (pinfunction "2_2") (pintype "unspecified"))
      (node (ref "Q3") (pin "5") (pinfunction "D_5") (pintype "unspecified"))
      (node (ref "Q3") (pin "6") (pinfunction "D_6") (pintype "unspecified"))
      (node (ref "Q3") (pin "7") (pinfunction "D_7") (pintype "unspecified"))
      (node (ref "Q3") (pin "8") (pinfunction "D_8") (pintype "unspecified"))
      (node (ref "U36") (pin "10") (pinfunction "VIN_10") (pintype "unspecified"))
      (node (ref "U36") (pin "11") (pinfunction "VIN_11") (pintype "unspecified"))
      (node (ref "U36") (pin "12") (pinfunction "VIN_12") (pintype "unspecified"))
      (node (ref "U36") (pin "9") (pinfunction "EN_9") (pintype "unspecified"))
    )
    (net (code "135") (name "Net-(U36-FB)") (class "Default")
      (node (ref "C70") (pin "2") (pinfunction "2_2") (pintype "input"))
      (node (ref "R85") (pin "1") (pinfunction "1_1") (pintype "input"))
      (node (ref "R86") (pin "2") (pinfunction "2_2") (pintype "input"))
      (node (ref "U36") (pin "7") (pinfunction "FB_7") (pintype "unspecified"))
    )
    (net (code "136") (name "Net-(U37-+IN)") (class "Default")
      (node (ref "C54") (pin "2") (pinfunction "2_2") (pintype "unspecified"))
      (node (ref "C55") (pin "2") (pinfunction "2_2") (pintype "unspecified"))
      (node (ref "R76") (pin "1") (pinfunction "1_1") (pintype "input"))
      (node (ref "U37") (pin "1") (pinfunction "+IN_1") (pintype "unspecified"))
    )
    (net (code "137") (name "Net-(U37--IN)") (class "Default")
      (node (ref "R74") (pin "1") (pinfunction "1_1") (pintype "unspecified"))
      (node (ref "U37") (pin "3") (pinfunction "-IN_3") (pintype "unspecified"))
      (node (ref "U37") (pin "4") (pinfunction "OUT_4") (pintype "output"))
    )
    (net (code "138") (name "Net-(U38-VOUT)") (class "Default")
      (node (ref "C53") (pin "1") (pinfunction "1_1") (pintype "input"))
      (node (ref "R76") (pin "2") (pinfunction "2_2") (pintype "input"))
      (node (ref "U38") (pin "4") (pinfunction "VOUT_4") (pintype "unspecified"))
    )
    (net (code "139") (name "Net-(U41-BOOT)") (class "Default")
      (node (ref "C76") (pin "1") (pinfunction "1_1") (pintype "unspecified"))
      (node (ref "U41") (pin "8") (pinfunction "BOOT_8") (pintype "unspecified"))
    )
    (net (code "140") (name "Net-(U41-COMP)") (class "Default")
      (node (ref "C83") (pin "1") (pinfunction "1_1") (pintype "input"))
      (node (ref "R91") (pin "1") (pinfunction "1_1") (pintype "input"))
      (node (ref "U41") (pin "18") (pinfunction "COMP_18") (pintype "unspecified"))
    )
    (net (code "141") (name "Net-(U41-FB)") (class "Default")
      (node (ref "R89") (pin "1") (pinfunction "1_1") (pintype "input"))
      (node (ref "R90") (pin "2") (pinfunction "2_2") (pintype "input"))
      (node (ref "U41") (pin "17") (pinfunction "FB_17") (pintype "unspecified"))
    )
    (net (code "142") (name "Net-(U41-FSW)") (class "Default")
      (node (ref "R88") (pin "2") (pinfunction "2_2") (pintype "input"))
      (node (ref "U41") (pin "3") (pinfunction "FSW_3") (pintype "unspecified"))
    )
    (net (code "143") (name "Net-(U41-ILIM)") (class "Default")
      (node (ref "R99") (pin "1") (pinfunction "1_1") (pintype "input"))
      (node (ref "U41") (pin "19") (pinfunction "ILIM_19") (pintype "unspecified"))
    )
    (net (code "144") (name "Net-(U41-SS)") (class "Default")
      (node (ref "C84") (pin "2") (pinfunction "2_2") (pintype "input"))
      (node (ref "U41") (pin "10") (pinfunction "SS_10") (pintype "unspecified"))
    )
    (net (code "145") (name "Net-(U41-VCC)") (class "Default")
      (node (ref "C77") (pin "2") (pinfunction "2_2") (pintype "input"))
      (node (ref "U41") (pin "1") (pinfunction "VCC_1") (pintype "unspecified"))
    )
    (net (code "146") (name "Net-(U42-EN)") (class "Default")
      (node (ref "R100") (pin "1") (pinfunction "1_1") (pintype "input"))
      (node (ref "U42") (pin "3") (pinfunction "EN_3") (pintype "unspecified"))
    )
    (net (code "147") (name "Net-(U43-PG)") (class "Default")
      (node (ref "R104") (pin "1") (pinfunction "1_1") (pintype "input"))
      (node (ref "U43") (pin "8") (pinfunction "PG_8") (pintype "unspecified"))
    )
    (net (code "148") (name "Net-(U43-SW)") (class "Default")
      (node (ref "L3") (pin "1") (pinfunction "1_1") (pintype "unspecified"))
      (node (ref "U43") (pin "7") (pinfunction "SW_7") (pintype "passive"))
    )
    (net (code "149") (name "Net-(U44-O1)") (class "Default")
      (node (ref "CN1") (pin "2") (pinfunction "2_2") (pintype "unspecified"))
      (node (ref "U44") (pin "16") (pinfunction "O1_16") (pintype "unspecified"))
    )
    (net (code "150") (name "Net-(U44-O2)") (class "Default")
      (node (ref "J2") (pin "2") (pinfunction "2_2") (pintype "unspecified"))
      (node (ref "U44") (pin "15") (pinfunction "O2_15") (pintype "unspecified"))
    )
    (net (code "151") (name "Net-(U44-O3)") (class "Default")
      (node (ref "J2") (pin "3") (pinfunction "3_3") (pintype "unspecified"))
      (node (ref "U44") (pin "14") (pinfunction "O3_14") (pintype "unspecified"))
    )
    (net (code "152") (name "Net-(U46-DELAY{slash}M_RST)") (class "Default")
      (node (ref "R92") (pin "2") (pinfunction "2_2") (pintype "input"))
      (node (ref "U46") (pin "3") (pinfunction "DELAY/M_RST_3") (pintype "unspecified"))
    )
    (net (code "153") (name "Net-(U48-RXD)") (class "Default")
      (node (ref "R96") (pin "2") (pinfunction "2_2") (pintype "input"))
      (node (ref "U48") (pin "3") (pinfunction "RXD_3") (pintype "unspecified"))
    )
    (net (code "154") (name "Net-(U51-CLK)") (class "Default")
      (node (ref "R105") (pin "2") (pinfunction "2_2") (pintype "input"))
      (node (ref "U51") (pin "1") (pinfunction "CLK_1") (pintype "unspecified"))
    )
    (net (code "155") (name "Net-(U51-D)") (class "Default")
      (node (ref "R106") (pin "2") (pinfunction "2_2") (pintype "input"))
      (node (ref "U51") (pin "2") (pinfunction "D_2") (pintype "unspecified"))
    )
    (net (code "156") (name "PDOWN") (class "Default")
      (node (ref "R75") (pin "1") (pinfunction "1_1") (pintype "input"))
      (node (ref "U35") (pin "14") (pinfunction "SYNCPDWN_14") (pintype "unspecified"))
      (node (ref "U49") (pin "11") (pinfunction "IO18_11") (pintype "unspecified"))
    )
    (net (code "157") (name "PG24") (class "Default")
      (node (ref "R84") (pin "1") (pinfunction "1_1") (pintype "input"))
      (node (ref "U36") (pin "5") (pinfunction "PG_5") (pintype "unspecified"))
      (node (ref "U49") (pin "26") (pinfunction "IO45_26") (pintype "unspecified"))
    )
    (net (code "158") (name "PRE") (class "Default")
      (node (ref "U51") (pin "7") (pinfunction "#PRE_7") (pintype "unspecified"))
      (node (ref "U52") (pin "4") (pinfunction "Y_4") (pintype "unspecified"))
    )
    (net (code "159") (name "RST") (class "Default")
      (node (ref "C91") (pin "2") (pinfunction "2_2") (pintype "unspecified"))
      (node (ref "Q1") (pin "6") (pinfunction "C1_6") (pintype "unspecified"))
      (node (ref "R95") (pin "1") (pinfunction "1_1") (pintype "input"))
      (node (ref "U46") (pin "6") (pinfunction "RSTn_6") (pintype "unspecified"))
      (node (ref "U49") (pin "3") (pinfunction "EN_3") (pintype "unspecified"))
    )
    (net (code "160") (name "RSTA") (class "Default")
      (node (ref "C66") (pin "2") (pinfunction "2_2") (pintype "unspecified"))
      (node (ref "R77") (pin "1") (pinfunction "1_1") (pintype "input"))
      (node (ref "U33") (pin "3") (pinfunction "RESET#_3") (pintype "unspecified"))
    )
    (net (code "161") (name "RTS") (class "Default")
      (node (ref "Q1") (pin "1") (pinfunction "E1_1") (pintype "unspecified"))
      (node (ref "Q1") (pin "5") (pinfunction "B2_5") (pintype "unspecified"))
      (node (ref "U48") (pin "14") (pinfunction "RTS#_14") (pintype "unspecified"))
    )
    (net (code "162") (name "RX2") (class "Default")
      (node (ref "U47") (pin "1") (pinfunction "R_1") (pintype "unspecified"))
      (node (ref "U49") (pin "14") (pinfunction "IO20_14") (pintype "unspecified"))
    )
    (net (code "163") (name "RXD") (class "Default")
      (node (ref "U48") (pin "2") (pinfunction "TXD_2") (pintype "unspecified"))
      (node (ref "U49") (pin "36") (pinfunction "RXD0_36") (pintype "unspecified"))
    )
    (net (code "164") (name "RXEN") (class "Default")
      (node (ref "U45") (pin "10") (pinfunction "RXEN_10") (pintype "unspecified"))
      (node (ref "U49") (pin "5") (pinfunction "IO5_5") (pintype "unspecified"))
    )
    (net (code "165") (name "SCL") (class "Default")
      (node (ref "R98") (pin "1") (pinfunction "1_1") (pintype "input"))
      (node (ref "U33") (pin "22") (pinfunction "SCL_22") (pintype "unspecified"))
      (node (ref "U49") (pin "17") (pinfunction "IO9_17") (pintype "unspecified"))
    )
    (net (code "166") (name "SCL0") (class "Default")
      (node (ref "U27") (pin "5") (pinfunction "SCL_5") (pintype "unspecified"))
      (node (ref "U33") (pin "5") (pinfunction "SC0_5") (pintype "unspecified"))
    )
    (net (code "167") (name "SCL1") (class "Default")
      (node (ref "U31") (pin "5") (pinfunction "SCL_5") (pintype "unspecified"))
      (node (ref "U33") (pin "7") (pinfunction "SC1_7") (pintype "unspecified"))
    )
    (net (code "168") (name "SCL2") (class "Default")
      (node (ref "U23") (pin "5") (pinfunction "SCL_5") (pintype "unspecified"))
      (node (ref "U33") (pin "9") (pinfunction "SC2_9") (pintype "unspecified"))
    )
    (net (code "169") (name "SCL3") (class "Default")
      (node (ref "U19") (pin "5") (pinfunction "SCL_5") (pintype "unspecified"))
      (node (ref "U33") (pin "11") (pinfunction "SC3_11") (pintype "unspecified"))
    )
    (net (code "170") (name "SCL4") (class "Default")
      (node (ref "U15") (pin "5") (pinfunction "SCL_5") (pintype "unspecified"))
      (node (ref "U33") (pin "14") (pinfunction "SC4_14") (pintype "unspecified"))
    )
    (net (code "171") (name "SCL5") (class "Default")
      (node (ref "U11") (pin "5") (pinfunction "SCL_5") (pintype "unspecified"))
      (node (ref "U33") (pin "16") (pinfunction "SC5_16") (pintype "unspecified"))
    )
    (net (code "172") (name "SCL6") (class "Default")
      (node (ref "U33") (pin "18") (pinfunction "SC6_18") (pintype "unspecified"))
      (node (ref "U6") (pin "5") (pinfunction "SCL_5") (pintype "unspecified"))
    )
    (net (code "173") (name "SCL7") (class "Default")
      (node (ref "U33") (pin "20") (pinfunction "SC7_20") (pintype "unspecified"))
      (node (ref "U8") (pin "5") (pinfunction "SCL_5") (pintype "unspecified"))
    )
    (net (code "174") (name "SDA") (class "Default")
      (node (ref "R97") (pin "1") (pinfunction "1_1") (pintype "input"))
      (node (ref "U33") (pin "23") (pinfunction "SDA_23") (pintype "unspecified"))
      (node (ref "U49") (pin "12") (pinfunction "IO8_12") (pintype "unspecified"))
    )
    (net (code "175") (name "SDA0") (class "Default")
      (node (ref "U27") (pin "4") (pinfunction "SDA_4") (pintype "unspecified"))
      (node (ref "U33") (pin "4") (pinfunction "SD0_4") (pintype "unspecified"))
    )
    (net (code "176") (name "SDA1") (class "Default")
      (node (ref "U31") (pin "4") (pinfunction "SDA_4") (pintype "unspecified"))
      (node (ref "U33") (pin "6") (pinfunction "SD1_6") (pintype "unspecified"))
    )
    (net (code "177") (name "SDA2") (class "Default")
      (node (ref "U23") (pin "4") (pinfunction "SDA_4") (pintype "unspecified"))
      (node (ref "U33") (pin "8") (pinfunction "SD2_8") (pintype "unspecified"))
    )
    (net (code "178") (name "SDA3") (class "Default")
      (node (ref "U19") (pin "4") (pinfunction "SDA_4") (pintype "unspecified"))
      (node (ref "U33") (pin "10") (pinfunction "SD3_10") (pintype "unspecified"))
    )
    (net (code "179") (name "SDA4") (class "Default")
      (node (ref "U15") (pin "4") (pinfunction "SDA_4") (pintype "unspecified"))
      (node (ref "U33") (pin "13") (pinfunction "SD4_13") (pintype "unspecified"))
    )
    (net (code "180") (name "SDA5") (class "Default")
      (node (ref "U11") (pin "4") (pinfunction "SDA_4") (pintype "unspecified"))
      (node (ref "U33") (pin "15") (pinfunction "SD5_15") (pintype "unspecified"))
    )
    (net (code "181") (name "SDA6") (class "Default")
      (node (ref "U33") (pin "17") (pinfunction "SD6_17") (pintype "unspecified"))
      (node (ref "U6") (pin "4") (pinfunction "SDA_4") (pintype "unspecified"))
    )
    (net (code "182") (name "SDA7") (class "Default")
      (node (ref "U33") (pin "19") (pinfunction "SD7_19") (pintype "unspecified"))
      (node (ref "U8") (pin "4") (pinfunction "SDA_4") (pintype "unspecified"))
    )
    (net (code "183") (name "SPI_CS") (class "Default")
      (node (ref "U35") (pin "20") (pinfunction "CS_20") (pintype "unspecified"))
      (node (ref "U49") (pin "24") (pinfunction "IO47_24") (pintype "unspecified"))
    )
    (net (code "184") (name "SPI_MISO") (class "Default")
      (node (ref "U35") (pin "22") (pinfunction "DOUT_22") (pintype "unspecified"))
      (node (ref "U45") (pin "12") (pinfunction "MISO_12") (pintype "unspecified"))
      (node (ref "U49") (pin "21") (pinfunction "IO13_21") (pintype "unspecified"))
    )
    (net (code "185") (name "SPI_MOSI") (class "Default")
      (node (ref "U35") (pin "23") (pinfunction "DIN_23") (pintype "unspecified"))
      (node (ref "U45") (pin "13") (pinfunction "MOSI_13") (pintype "unspecified"))
      (node (ref "U49") (pin "19") (pinfunction "IO11_19") (pintype "unspecified"))
    )
    (net (code "186") (name "SPI_SCK") (class "Default")
      (node (ref "U35") (pin "24") (pinfunction "SCLK_24") (pintype "unspecified"))
      (node (ref "U45") (pin "15") (pinfunction "SCK_15") (pintype "unspecified"))
      (node (ref "U49") (pin "20") (pinfunction "IO12_20") (pintype "unspecified"))
    )
    (net (code "187") (name "TX2") (class "Default")
      (node (ref "U47") (pin "4") (pinfunction "D_4") (pintype "unspecified"))
      (node (ref "U49") (pin "23") (pinfunction "IO21_23") (pintype "unspecified"))
    )
    (net (code "188") (name "TXD") (class "Default")
      (node (ref "R96") (pin "1") (pinfunction "1_1") (pintype "input"))
      (node (ref "U49") (pin "37") (pinfunction "TXD0_37") (pintype "unspecified"))
    )
    (net (code "189") (name "TXEN") (class "Default")
      (node (ref "U45") (pin "9") (pinfunction "TXEN_9") (pintype "unspecified"))
      (node (ref "U49") (pin "6") (pinfunction "IO6_6") (pintype "unspecified"))
    )
    (net (code "190") (name "VBAT") (class "Default")
      (node (ref "C74") (pin "2") (pinfunction "2_2") (pintype "unspecified"))
      (node (ref "C75") (pin "2") (pinfunction "2_2") (pintype "unspecified"))
      (node (ref "D3") (pin "1") (pinfunction "A1_1") (pintype "unspecified"))
      (node (ref "J1") (pin "2") (pinfunction "2_2") (pintype "input"))
      (node (ref "L2") (pin "1") (pinfunction "1_1") (pintype "unspecified"))
      (node (ref "R83") (pin "2") (pinfunction "2_2") (pintype "input"))
      (node (ref "U41") (pin "9") (pinfunction "VIN_9") (pintype "unspecified"))
    )
    (net (code "191") (name "VBUS") (class "Default")
      (node (ref "USB1") (pin "1") (pinfunction "VBUS_1") (pintype "unspecified"))
    )
    (net (code "192") (name "VCC") (class "Default")
      (node (ref "C58") (pin "2") (pinfunction "2_2") (pintype "unspecified"))
      (node (ref "C85") (pin "2") (pinfunction "2_2") (pintype "unspecified"))
      (node (ref "C86") (pin "2") (pinfunction "2_2") (pintype "unspecified"))
      (node (ref "C87") (pin "2") (pinfunction "2_2") (pintype "unspecified"))
      (node (ref "C88") (pin "2") (pinfunction "2_2") (pintype "unspecified"))
      (node (ref "C89") (pin "2") (pinfunction "2_2") (pintype "unspecified"))
      (node (ref "C92") (pin "2") (pinfunction "2_2") (pintype "unspecified"))
      (node (ref "C93") (pin "2") (pinfunction "2_2") (pintype "input"))
      (node (ref "C95") (pin "2") (pinfunction "2_2") (pintype "unspecified"))
      (node (ref "C96") (pin "2") (pinfunction "2_2") (pintype "unspecified"))
      (node (ref "L3") (pin "2") (pinfunction "2_2") (pintype "unspecified"))
      (node (ref "LED1") (pin "1") (pinfunction "A_1") (pintype "input"))
      (node (ref "R104") (pin "2") (pinfunction "2_2") (pintype "input"))
      (node (ref "R73") (pin "2") (pinfunction "2_2") (pintype "input"))
      (node (ref "R75") (pin "2") (pinfunction "2_2") (pintype "input"))
      (node (ref "R80") (pin "1") (pinfunction "1_1") (pintype "input"))
      (node (ref "R84") (pin "2") (pinfunction "2_2") (pintype "input"))
      (node (ref "R94") (pin "2") (pinfunction "2_2") (pintype "input"))
      (node (ref "R95") (pin "2") (pinfunction "2_2") (pintype "input"))
      (node (ref "R97") (pin "2") (pinfunction "2_2") (pintype "input"))
      (node (ref "R98") (pin "2") (pinfunction "2_2") (pintype "input"))
      (node (ref "U35") (pin "16") (pinfunction "DVDD_16") (pintype "passive"))
      (node (ref "U43") (pin "6") (pinfunction "VOS_6") (pintype "unspecified"))
      (node (ref "U45") (pin "1") (pinfunction "VCC_1") (pintype "unspecified"))
      (node (ref "U47") (pin "8") (pinfunction "VCC_8") (pintype "unspecified"))
      (node (ref "U48") (pin "16") (pinfunction "VCC_16") (pintype "unspecified"))
      (node (ref "U48") (pin "4") (pinfunction "V3_4") (pintype "unspecified"))
      (node (ref "U49") (pin "2") (pinfunction "3V3_2") (pintype "passive"))
    )
    (net (code "193") (name "VREF") (class "Default")
      (node (ref "C51") (pin "2") (pinfunction "2_2") (pintype "unspecified"))
      (node (ref "C56") (pin "1") (pinfunction "1_1") (pintype "input"))
      (node (ref "R74") (pin "2") (pinfunction "2_2") (pintype "unspecified"))
      (node (ref "U35") (pin "4") (pinfunction "VREFP_4") (pintype "unspecified"))
    )
    (net (code "194") (name "WAKE") (class "Default")
      (node (ref "U46") (pin "5") (pinfunction "WAKE_5") (pintype "unspecified"))
      (node (ref "U52") (pin "2") (pinfunction "A_2") (pintype "unspecified"))
    )
    (net (code "195") (name "unconnected-(U1-NC-Pad4)") (class "Default")
      (node (ref "U1") (pin "4") (pinfunction "NC_4") (pintype "unspecified+no_connect"))
    )
    (net (code "196") (name "unconnected-(U7-NC-Pad4)") (class "Default")
      (node (ref "U7") (pin "4") (pinfunction "NC_4") (pintype "unspecified+no_connect"))
    )
    (net (code "197") (name "unconnected-(U12-NC-Pad4)") (class "Default")
      (node (ref "U12") (pin "4") (pinfunction "NC_4") (pintype "unspecified+no_connect"))
    )
    (net (code "198") (name "unconnected-(U16-NC-Pad4)") (class "Default")
      (node (ref "U16") (pin "4") (pinfunction "NC_4") (pintype "unspecified+no_connect"))
    )
    (net (code "199") (name "unconnected-(U20-NC-Pad4)") (class "Default")
      (node (ref "U20") (pin "4") (pinfunction "NC_4") (pintype "unspecified+no_connect"))
    )
    (net (code "200") (name "unconnected-(U24-NC-Pad4)") (class "Default")
      (node (ref "U24") (pin "4") (pinfunction "NC_4") (pintype "unspecified+no_connect"))
    )
    (net (code "201") (name "unconnected-(U28-NC-Pad4)") (class "Default")
      (node (ref "U28") (pin "4") (pinfunction "NC_4") (pintype "unspecified+no_connect"))
    )
    (net (code "202") (name "unconnected-(U32-NC-Pad4)") (class "Default")
      (node (ref "U32") (pin "4") (pinfunction "NC_4") (pintype "unspecified+no_connect"))
    )
    (net (code "203") (name "unconnected-(U35-D0CLKOUT-Pad25)") (class "Default")
      (node (ref "U35") (pin "25") (pinfunction "D0CLKOUT_25") (pintype "bidirectional+no_connect"))
    )
    (net (code "204") (name "unconnected-(U35-D1-Pad26)") (class "Default")
      (node (ref "U35") (pin "26") (pinfunction "D1_26") (pintype "bidirectional+no_connect"))
    )
    (net (code "205") (name "unconnected-(U35-D2-Pad27)") (class "Default")
      (node (ref "U35") (pin "27") (pinfunction "D2_27") (pintype "bidirectional+no_connect"))
    )
    (net (code "206") (name "unconnected-(U35-D3-Pad28)") (class "Default")
      (node (ref "U35") (pin "28") (pinfunction "D3_28") (pintype "bidirectional+no_connect"))
    )
    (net (code "207") (name "unconnected-(U36-RT-Pad6)") (class "Default")
      (node (ref "U36") (pin "6") (pinfunction "RT_6") (pintype "unspecified+no_connect"))
    )
    (net (code "208") (name "unconnected-(U38-TEMP-Pad1)") (class "Default")
      (node (ref "U38") (pin "1") (pinfunction "TEMP_1") (pintype "unspecified+no_connect"))
    )
    (net (code "209") (name "unconnected-(U38-TRIM-Pad5)") (class "Default")
      (node (ref "U38") (pin "5") (pinfunction "TRIM_5") (pintype "unspecified+no_connect"))
    )
    (net (code "210") (name "unconnected-(U41-MODE-Pad13)") (class "Default")
      (node (ref "U41") (pin "13") (pinfunction "MODE_13") (pintype "unspecified+no_connect"))
    )
    (net (code "211") (name "unconnected-(U41-NC-Pad11)") (class "Default")
      (node (ref "U41") (pin "11") (pinfunction "NC_11") (pintype "unspecified+no_connect"))
    )
    (net (code "212") (name "unconnected-(U41-NC-Pad12)") (class "Default")
      (node (ref "U41") (pin "12") (pinfunction "NC_12") (pintype "unspecified+no_connect"))
    )
    (net (code "213") (name "unconnected-(U42-NC-Pad4)") (class "Default")
      (node (ref "U42") (pin "4") (pinfunction "NC_4") (pintype "unspecified+no_connect"))
    )
    (net (code "214") (name "unconnected-(U44-I4-Pad4)") (class "Default")
      (node (ref "U44") (pin "4") (pinfunction "I4_4") (pintype "unspecified"))
    )
    (net (code "215") (name "unconnected-(U44-I5-Pad5)") (class "Default")
      (node (ref "U44") (pin "5") (pinfunction "I5_5") (pintype "unspecified"))
    )
    (net (code "216") (name "unconnected-(U44-I6-Pad6)") (class "Default")
      (node (ref "U44") (pin "6") (pinfunction "I6_6") (pintype "unspecified"))
    )
    (net (code "217") (name "unconnected-(U44-I7-Pad7)") (class "Default")
      (node (ref "U44") (pin "7") (pinfunction "I7_7") (pintype "unspecified"))
    )
    (net (code "218") (name "unconnected-(U44-O4-Pad13)") (class "Default")
      (node (ref "U44") (pin "13") (pinfunction "O4_13") (pintype "unspecified"))
    )
    (net (code "219") (name "unconnected-(U44-O5-Pad12)") (class "Default")
      (node (ref "U44") (pin "12") (pinfunction "O5_12") (pintype "unspecified"))
    )
    (net (code "220") (name "unconnected-(U44-O6-Pad11)") (class "Default")
      (node (ref "U44") (pin "11") (pinfunction "O6_11") (pintype "unspecified"))
    )
    (net (code "221") (name "unconnected-(U44-O7-Pad10)") (class "Default")
      (node (ref "U44") (pin "10") (pinfunction "O7_10") (pintype "unspecified"))
    )
    (net (code "222") (name "unconnected-(U45-DIO2-Pad19)") (class "Default")
      (node (ref "U45") (pin "19") (pinfunction "DIO2_19") (pintype "unspecified"))
    )
    (net (code "223") (name "unconnected-(U45-DIO3-Pad18)") (class "Default")
      (node (ref "U45") (pin "18") (pinfunction "DIO3_18") (pintype "unspecified"))
    )
    (net (code "224") (name "unconnected-(U45-NC-Pad4)") (class "Default")
      (node (ref "U45") (pin "4") (pinfunction "NC_4") (pintype "unspecified+no_connect"))
    )
    (net (code "225") (name "unconnected-(U45-NC-Pad5)") (class "Default")
      (node (ref "U45") (pin "5") (pinfunction "NC_5") (pintype "unspecified+no_connect"))
    )
    (net (code "226") (name "unconnected-(U45-NC-Pad8)") (class "Default")
      (node (ref "U45") (pin "8") (pinfunction "NC_8") (pintype "unspecified+no_connect"))
    )
    (net (code "227") (name "unconnected-(U45-NC-Pad17)") (class "Default")
      (node (ref "U45") (pin "17") (pinfunction "NC_17") (pintype "unspecified+no_connect"))
    )
    (net (code "228") (name "unconnected-(U48-CTS#-Pad9)") (class "Default")
      (node (ref "U48") (pin "9") (pinfunction "CTS#_9") (pintype "unspecified"))
    )
    (net (code "229") (name "unconnected-(U48-DCD#-Pad12)") (class "Default")
      (node (ref "U48") (pin "12") (pinfunction "DCD#_12") (pintype "unspecified"))
    )
    (net (code "230") (name "unconnected-(U48-DSR#-Pad10)") (class "Default")
      (node (ref "U48") (pin "10") (pinfunction "DSR#_10") (pintype "unspecified"))
    )
    (net (code "231") (name "unconnected-(U48-NC.-Pad7)") (class "Default")
      (node (ref "U48") (pin "7") (pinfunction "NC._7") (pintype "unspecified+no_connect"))
    )
    (net (code "232") (name "unconnected-(U48-NC.-Pad8)") (class "Default")
      (node (ref "U48") (pin "8") (pinfunction "NC._8") (pintype "unspecified+no_connect"))
    )
    (net (code "233") (name "unconnected-(U48-R232-Pad15)") (class "Default")
      (node (ref "U48") (pin "15") (pinfunction "R232_15") (pintype "unspecified"))
    )
    (net (code "234") (name "unconnected-(U48-RI#-Pad11)") (class "Default")
      (node (ref "U48") (pin "11") (pinfunction "RI#_11") (pintype "unspecified"))
    )
    (net (code "235") (name "unconnected-(U49-IO3-Pad15)") (class "Default")
      (node (ref "U49") (pin "15") (pinfunction "IO3_15") (pintype "unspecified"))
    )
    (net (code "236") (name "unconnected-(U49-IO17-Pad10)") (class "Default")
      (node (ref "U49") (pin "10") (pinfunction "IO17_10") (pintype "unspecified"))
    )
    (net (code "237") (name "unconnected-(U49-IO35-Pad28)") (class "Default")
      (node (ref "U49") (pin "28") (pinfunction "IO35_28") (pintype "unspecified"))
    )
    (net (code "238") (name "unconnected-(U49-IO36-Pad29)") (class "Default")
      (node (ref "U49") (pin "29") (pinfunction "IO36_29") (pintype "unspecified"))
    )
    (net (code "239") (name "unconnected-(U49-IO37-Pad30)") (class "Default")
      (node (ref "U49") (pin "30") (pinfunction "IO37_30") (pintype "unspecified"))
    )
    (net (code "240") (name "unconnected-(U49-IO46-Pad16)") (class "Default")
      (node (ref "U49") (pin "16") (pinfunction "IO46_16") (pintype "unspecified"))
    )
    (net (code "241") (name "unconnected-(U49-IO48-Pad25)") (class "Default")
      (node (ref "U49") (pin "25") (pinfunction "IO48_25") (pintype "unspecified"))
    )
    (net (code "242") (name "unconnected-(U51-#Q-Pad3)") (class "Default")
      (node (ref "U51") (pin "3") (pinfunction "#Q_3") (pintype "unspecified+no_connect"))
    )
    (net (code "243") (name "unconnected-(U52-NC-Pad1)") (class "Default")
      (node (ref "U52") (pin "1") (pinfunction "NC_1") (pintype "unspecified+no_connect"))
    )
    (net (code "244") (name "unconnected-(USB1-ID-Pad4)") (class "Default")
      (node (ref "USB1") (pin "4") (pinfunction "ID_4") (pintype "unspecified+no_connect"))
    )
  )
)
